# PowerBoardOld.net
KiCad netlist of a schematic drawn in Altium Designer
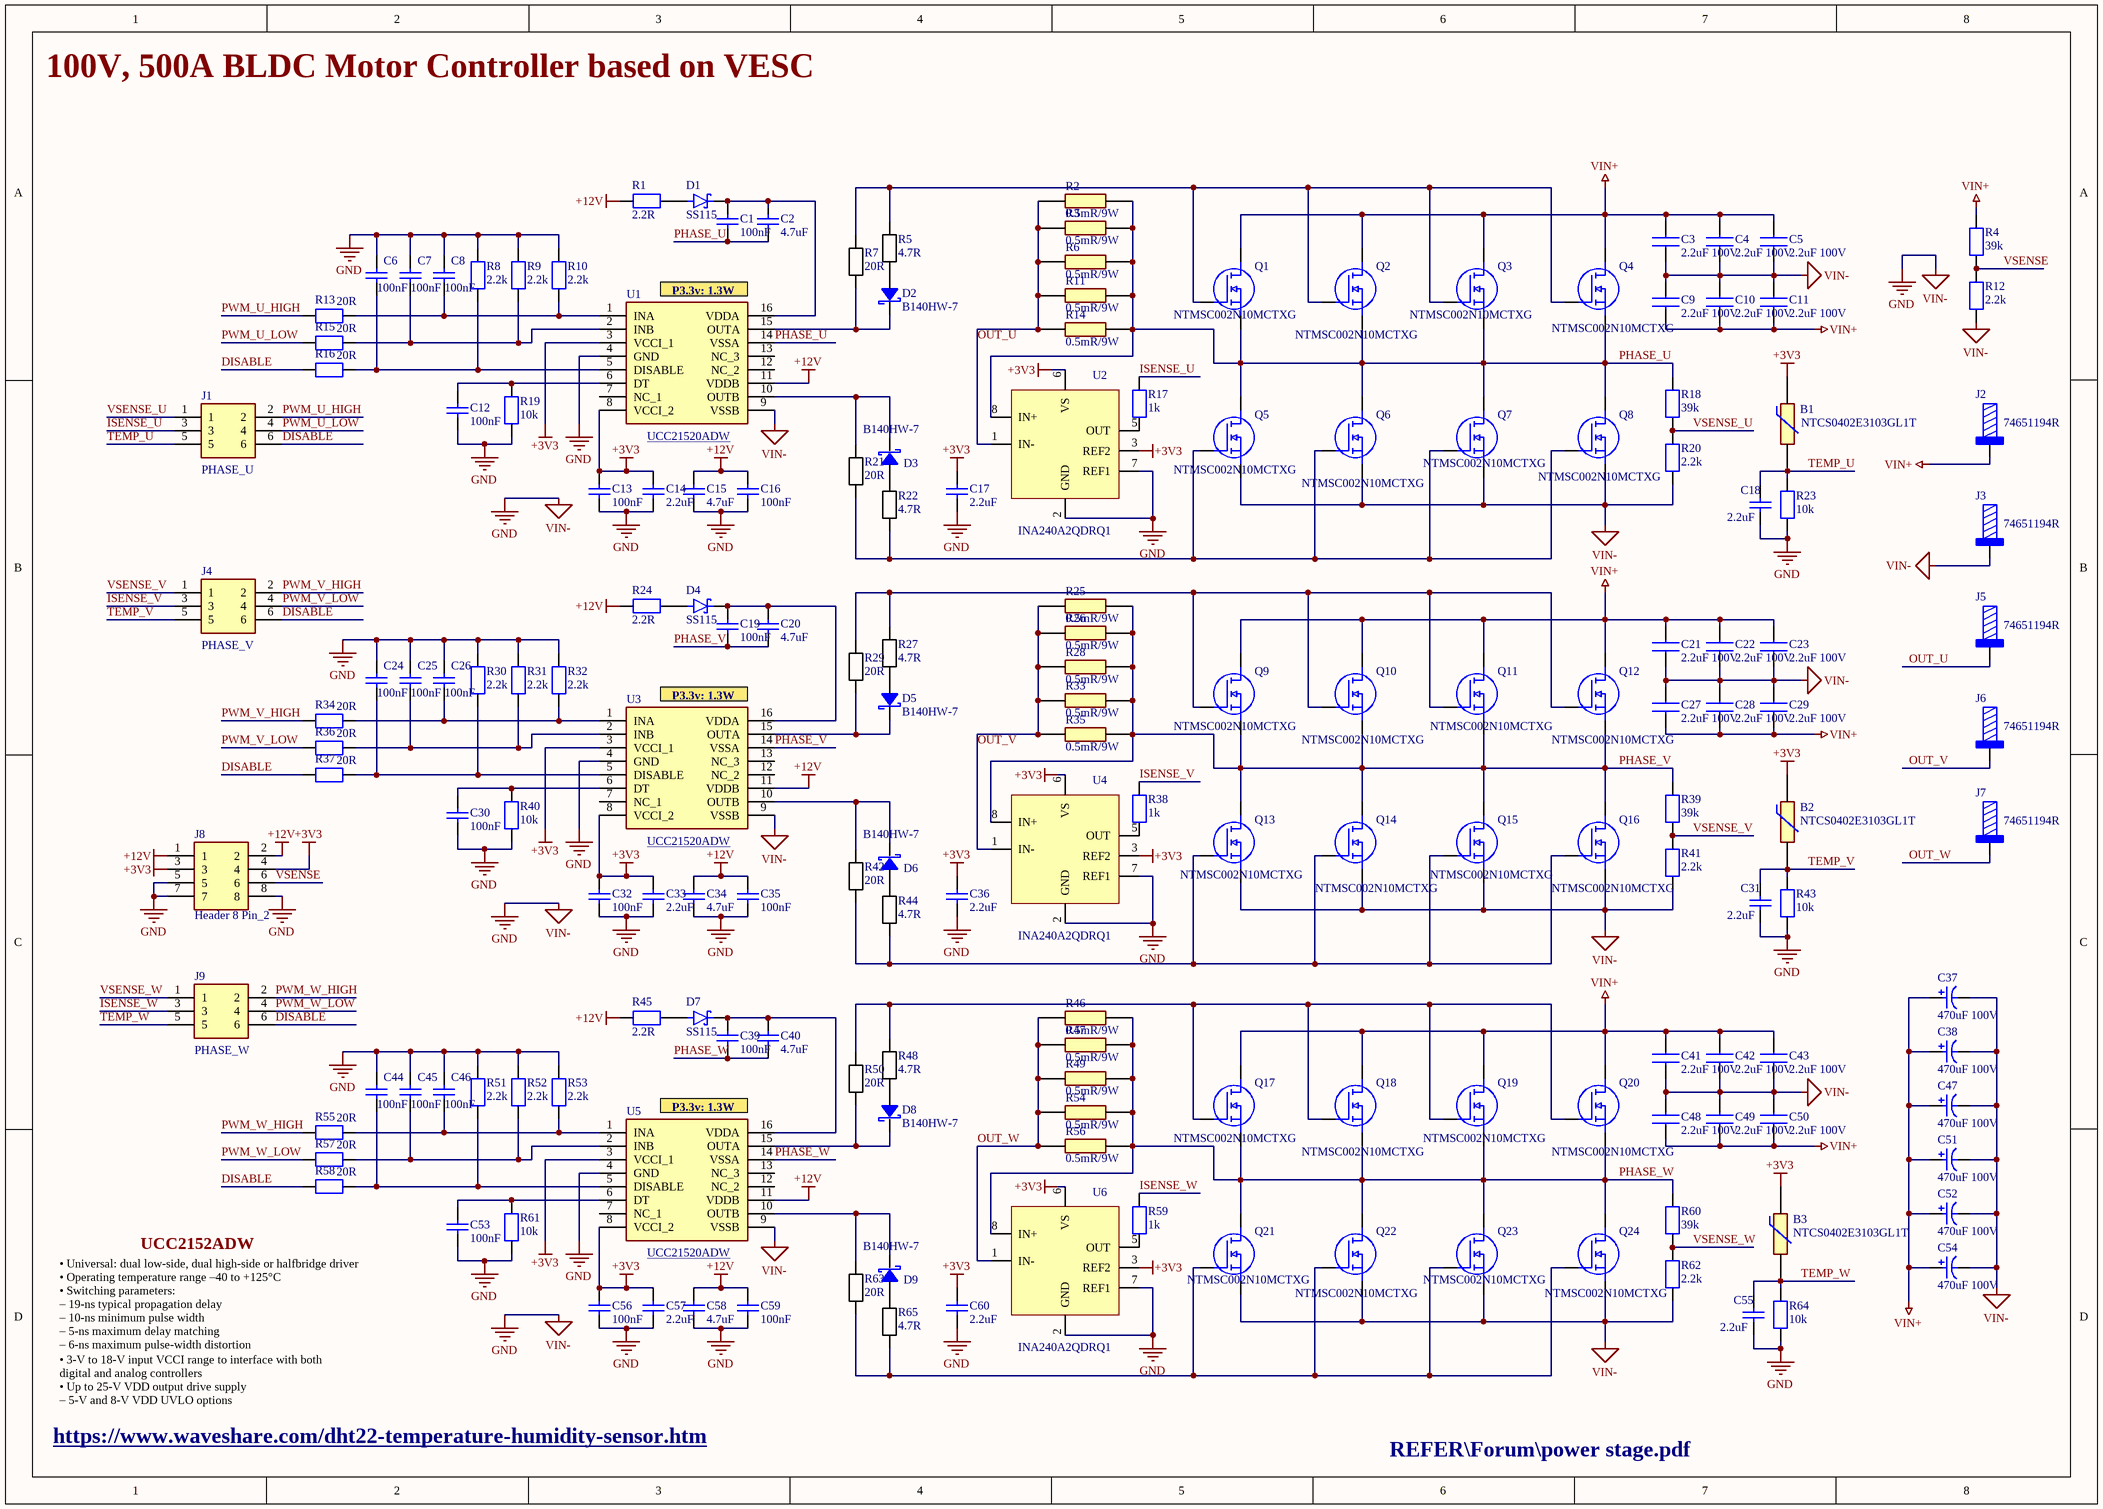
[diagram p0: PowerBoardOld.SchDoc]

(export (version "E")
  (design (tool "Eeschema 10.0.6"))
  (components
    (comp (ref "B1")
      (value "NTCS0402E3103GL1T")
      (footprint "THRMC1005X65N")
      (description "NTC Thermistors 10Kohms 2% AEC-Q200")
      (fields (field (name "MANUFACTURER") "Vishay"))
      (libsource (lib "VESC_MotorController") (part "NTCS0402E3103GL1T"))
    )
    (comp (ref "B2")
      (value "NTCS0402E3103GL1T")
      (footprint "THRMC1005X65N")
      (description "NTC Thermistors 10Kohms 2% AEC-Q200")
      (fields (field (name "MANUFACTURER") "Vishay"))
      (libsource (lib "VESC_MotorController") (part "NTCS0402E3103GL1T"))
    )
    (comp (ref "B3")
      (value "NTCS0402E3103GL1T")
      (footprint "THRMC1005X65N")
      (description "NTC Thermistors 10Kohms 2% AEC-Q200")
      (fields (field (name "MANUFACTURER") "Vishay"))
      (libsource (lib "VESC_MotorController") (part "NTCS0402E3103GL1T"))
    )
    (comp (ref "C1")
      (value "100nF")
      (footprint "C0402")
      (description "100nF ± 10% 50V")
      (fields
        (field (name "MANUFACTURER") "Yageo")
        (field (name "MANUFACTURER PART NUMBER") "CS0603KRX7R9BB104")
      )
      (libsource (lib "VESC_MotorController") (part "100nF ± 10% 50V"))
    )
    (comp (ref "C2")
      (value "4.7uF")
      (footprint "C0603")
      (description "4.7uF ± 10% 50V")
      (fields
        (field (name "MANUFACTURER") "Yageo")
        (field (name "MANUFACTURER PART NUMBER") "GRM188R61H225ME11J")
      )
      (libsource (lib "VESC_MotorController") (part "4.7uF ± 10% 50V"))
    )
    (comp (ref "C3")
      (value "2.2uF 100V")
      (footprint "CAPC3216X178N")
      (description "Multilayer Ceramic Capacitors MLCC - SMD/SMT 100V 2.2uF X7R 1206 20%TOL HIGH CV")
      (fields
        (field (name "MANUFACTURER") "KYOCERA AVX")
        (field (name "MANUFACTURER PART NUMBER") "12061C225MAT2A")
      )
      (libsource (lib "VESC_MotorController") (part "2.2uF ±10% 100V"))
    )
    (comp (ref "C4")
      (value "2.2uF 100V")
      (footprint "CAPC3216X178N")
      (description "Multilayer Ceramic Capacitors MLCC - SMD/SMT 100V 2.2uF X7R 1206 20%TOL HIGH CV")
      (fields
        (field (name "MANUFACTURER") "KYOCERA AVX")
        (field (name "MANUFACTURER PART NUMBER") "12061C225MAT2A")
      )
      (libsource (lib "VESC_MotorController") (part "2.2uF ±10% 100V"))
    )
    (comp (ref "C5")
      (value "2.2uF 100V")
      (footprint "CAPC3216X178N")
      (description "Multilayer Ceramic Capacitors MLCC - SMD/SMT 100V 2.2uF X7R 1206 20%TOL HIGH CV")
      (fields
        (field (name "MANUFACTURER") "KYOCERA AVX")
        (field (name "MANUFACTURER PART NUMBER") "12061C225MAT2A")
      )
      (libsource (lib "VESC_MotorController") (part "2.2uF ±10% 100V"))
    )
    (comp (ref "C6")
      (value "100nF")
      (footprint "C0402")
      (description "100nF ± 10% 50V")
      (fields
        (field (name "MANUFACTURER") "Yageo")
        (field (name "MANUFACTURER PART NUMBER") "CS0603KRX7R9BB104")
      )
      (libsource (lib "VESC_MotorController") (part "100nF ± 10% 50V"))
    )
    (comp (ref "C7")
      (value "100nF")
      (footprint "C0402")
      (description "100nF ± 10% 50V")
      (fields
        (field (name "MANUFACTURER") "Yageo")
        (field (name "MANUFACTURER PART NUMBER") "CS0603KRX7R9BB104")
      )
      (libsource (lib "VESC_MotorController") (part "100nF ± 10% 50V"))
    )
    (comp (ref "C8")
      (value "100nF")
      (footprint "C0402")
      (description "100nF ± 10% 50V")
      (fields
        (field (name "MANUFACTURER") "Yageo")
        (field (name "MANUFACTURER PART NUMBER") "CS0603KRX7R9BB104")
      )
      (libsource (lib "VESC_MotorController") (part "100nF ± 10% 50V"))
    )
    (comp (ref "C9")
      (value "2.2uF 100V")
      (footprint "CAPC3216X178N")
      (description "Multilayer Ceramic Capacitors MLCC - SMD/SMT 100V 2.2uF X7R 1206 20%TOL HIGH CV")
      (fields
        (field (name "MANUFACTURER") "KYOCERA AVX")
        (field (name "MANUFACTURER PART NUMBER") "12061C225MAT2A")
      )
      (libsource (lib "VESC_MotorController") (part "2.2uF ±10% 100V"))
    )
    (comp (ref "C10")
      (value "2.2uF 100V")
      (footprint "CAPC3216X178N")
      (description "Multilayer Ceramic Capacitors MLCC - SMD/SMT 100V 2.2uF X7R 1206 20%TOL HIGH CV")
      (fields
        (field (name "MANUFACTURER") "KYOCERA AVX")
        (field (name "MANUFACTURER PART NUMBER") "12061C225MAT2A")
      )
      (libsource (lib "VESC_MotorController") (part "2.2uF ±10% 100V"))
    )
    (comp (ref "C11")
      (value "2.2uF 100V")
      (footprint "CAPC3216X178N")
      (description "Multilayer Ceramic Capacitors MLCC - SMD/SMT 100V 2.2uF X7R 1206 20%TOL HIGH CV")
      (fields
        (field (name "MANUFACTURER") "KYOCERA AVX")
        (field (name "MANUFACTURER PART NUMBER") "12061C225MAT2A")
      )
      (libsource (lib "VESC_MotorController") (part "2.2uF ±10% 100V"))
    )
    (comp (ref "C12")
      (value "100nF")
      (footprint "C0402")
      (description "100nF ± 10% 50V")
      (fields
        (field (name "MANUFACTURER") "Yageo")
        (field (name "MANUFACTURER PART NUMBER") "CS0603KRX7R9BB104")
      )
      (libsource (lib "VESC_MotorController") (part "100nF ± 10% 50V"))
    )
    (comp (ref "C13")
      (value "100nF")
      (footprint "C0402")
      (description "100nF ± 10% 50V")
      (fields
        (field (name "MANUFACTURER") "Yageo")
        (field (name "MANUFACTURER PART NUMBER") "CS0603KRX7R9BB104")
      )
      (libsource (lib "VESC_MotorController") (part "100nF ± 10% 50V"))
    )
    (comp (ref "C14")
      (value "2.2uF")
      (footprint "C0603")
      (description "2.2uF ± 10% 50V")
      (fields
        (field (name "MANUFACTURER") "Yageo")
        (field (name "MANUFACTURER PART NUMBER") "GRM188R61H225ME11J")
      )
      (libsource (lib "VESC_MotorController") (part "2.2uF ± 10% 50V"))
    )
    (comp (ref "C15")
      (value "4.7uF")
      (footprint "C0603")
      (description "4.7uF ± 10% 50V")
      (fields
        (field (name "MANUFACTURER") "Yageo")
        (field (name "MANUFACTURER PART NUMBER") "GRM188R61H225ME11J")
      )
      (libsource (lib "VESC_MotorController") (part "4.7uF ± 10% 50V"))
    )
    (comp (ref "C16")
      (value "100nF")
      (footprint "C0402")
      (description "100nF ± 10% 50V")
      (fields
        (field (name "MANUFACTURER") "Yageo")
        (field (name "MANUFACTURER PART NUMBER") "CS0603KRX7R9BB104")
      )
      (libsource (lib "VESC_MotorController") (part "100nF ± 10% 50V"))
    )
    (comp (ref "C17")
      (value "2.2uF")
      (footprint "C0603")
      (description "2.2uF ± 10% 50V")
      (fields
        (field (name "MANUFACTURER") "Yageo")
        (field (name "MANUFACTURER PART NUMBER") "GRM188R61H225ME11J")
      )
      (libsource (lib "VESC_MotorController") (part "2.2uF ± 10% 50V"))
    )
    (comp (ref "C18")
      (value "2.2uF")
      (footprint "C0603")
      (description "2.2uF ± 10% 50V")
      (fields
        (field (name "MANUFACTURER") "Yageo")
        (field (name "MANUFACTURER PART NUMBER") "GRM188R61H225ME11J")
      )
      (libsource (lib "VESC_MotorController") (part "2.2uF ± 10% 50V"))
    )
    (comp (ref "C19")
      (value "100nF")
      (footprint "C0402")
      (description "100nF ± 10% 50V")
      (fields
        (field (name "MANUFACTURER") "Yageo")
        (field (name "MANUFACTURER PART NUMBER") "CS0603KRX7R9BB104")
      )
      (libsource (lib "VESC_MotorController") (part "100nF ± 10% 50V"))
    )
    (comp (ref "C20")
      (value "4.7uF")
      (footprint "C0603")
      (description "4.7uF ± 10% 50V")
      (fields
        (field (name "MANUFACTURER") "Yageo")
        (field (name "MANUFACTURER PART NUMBER") "GRM188R61H225ME11J")
      )
      (libsource (lib "VESC_MotorController") (part "4.7uF ± 10% 50V"))
    )
    (comp (ref "C21")
      (value "2.2uF 100V")
      (footprint "CAPC3216X178N")
      (description "Multilayer Ceramic Capacitors MLCC - SMD/SMT 100V 2.2uF X7R 1206 20%TOL HIGH CV")
      (fields
        (field (name "MANUFACTURER") "KYOCERA AVX")
        (field (name "MANUFACTURER PART NUMBER") "12061C225MAT2A")
      )
      (libsource (lib "VESC_MotorController") (part "2.2uF ±10% 100V"))
    )
    (comp (ref "C22")
      (value "2.2uF 100V")
      (footprint "CAPC3216X178N")
      (description "Multilayer Ceramic Capacitors MLCC - SMD/SMT 100V 2.2uF X7R 1206 20%TOL HIGH CV")
      (fields
        (field (name "MANUFACTURER") "KYOCERA AVX")
        (field (name "MANUFACTURER PART NUMBER") "12061C225MAT2A")
      )
      (libsource (lib "VESC_MotorController") (part "2.2uF ±10% 100V"))
    )
    (comp (ref "C23")
      (value "2.2uF 100V")
      (footprint "CAPC3216X178N")
      (description "Multilayer Ceramic Capacitors MLCC - SMD/SMT 100V 2.2uF X7R 1206 20%TOL HIGH CV")
      (fields
        (field (name "MANUFACTURER") "KYOCERA AVX")
        (field (name "MANUFACTURER PART NUMBER") "12061C225MAT2A")
      )
      (libsource (lib "VESC_MotorController") (part "2.2uF ±10% 100V"))
    )
    (comp (ref "C24")
      (value "100nF")
      (footprint "C0402")
      (description "100nF ± 10% 50V")
      (fields
        (field (name "MANUFACTURER") "Yageo")
        (field (name "MANUFACTURER PART NUMBER") "CS0603KRX7R9BB104")
      )
      (libsource (lib "VESC_MotorController") (part "100nF ± 10% 50V"))
    )
    (comp (ref "C25")
      (value "100nF")
      (footprint "C0402")
      (description "100nF ± 10% 50V")
      (fields
        (field (name "MANUFACTURER") "Yageo")
        (field (name "MANUFACTURER PART NUMBER") "CS0603KRX7R9BB104")
      )
      (libsource (lib "VESC_MotorController") (part "100nF ± 10% 50V"))
    )
    (comp (ref "C26")
      (value "100nF")
      (footprint "C0402")
      (description "100nF ± 10% 50V")
      (fields
        (field (name "MANUFACTURER") "Yageo")
        (field (name "MANUFACTURER PART NUMBER") "CS0603KRX7R9BB104")
      )
      (libsource (lib "VESC_MotorController") (part "100nF ± 10% 50V"))
    )
    (comp (ref "C27")
      (value "2.2uF 100V")
      (footprint "CAPC3216X178N")
      (description "Multilayer Ceramic Capacitors MLCC - SMD/SMT 100V 2.2uF X7R 1206 20%TOL HIGH CV")
      (fields
        (field (name "MANUFACTURER") "KYOCERA AVX")
        (field (name "MANUFACTURER PART NUMBER") "12061C225MAT2A")
      )
      (libsource (lib "VESC_MotorController") (part "2.2uF ±10% 100V"))
    )
    (comp (ref "C28")
      (value "2.2uF 100V")
      (footprint "CAPC3216X178N")
      (description "Multilayer Ceramic Capacitors MLCC - SMD/SMT 100V 2.2uF X7R 1206 20%TOL HIGH CV")
      (fields
        (field (name "MANUFACTURER") "KYOCERA AVX")
        (field (name "MANUFACTURER PART NUMBER") "12061C225MAT2A")
      )
      (libsource (lib "VESC_MotorController") (part "2.2uF ±10% 100V"))
    )
    (comp (ref "C29")
      (value "2.2uF 100V")
      (footprint "CAPC3216X178N")
      (description "Multilayer Ceramic Capacitors MLCC - SMD/SMT 100V 2.2uF X7R 1206 20%TOL HIGH CV")
      (fields
        (field (name "MANUFACTURER") "KYOCERA AVX")
        (field (name "MANUFACTURER PART NUMBER") "12061C225MAT2A")
      )
      (libsource (lib "VESC_MotorController") (part "2.2uF ±10% 100V"))
    )
    (comp (ref "C30")
      (value "100nF")
      (footprint "C0402")
      (description "100nF ± 10% 50V")
      (fields
        (field (name "MANUFACTURER") "Yageo")
        (field (name "MANUFACTURER PART NUMBER") "CS0603KRX7R9BB104")
      )
      (libsource (lib "VESC_MotorController") (part "100nF ± 10% 50V"))
    )
    (comp (ref "C31")
      (value "2.2uF")
      (footprint "C0603")
      (description "2.2uF ± 10% 50V")
      (fields
        (field (name "MANUFACTURER") "Yageo")
        (field (name "MANUFACTURER PART NUMBER") "GRM188R61H225ME11J")
      )
      (libsource (lib "VESC_MotorController") (part "2.2uF ± 10% 50V"))
    )
    (comp (ref "C32")
      (value "100nF")
      (footprint "C0402")
      (description "100nF ± 10% 50V")
      (fields
        (field (name "MANUFACTURER") "Yageo")
        (field (name "MANUFACTURER PART NUMBER") "CS0603KRX7R9BB104")
      )
      (libsource (lib "VESC_MotorController") (part "100nF ± 10% 50V"))
    )
    (comp (ref "C33")
      (value "2.2uF")
      (footprint "C0603")
      (description "2.2uF ± 10% 50V")
      (fields
        (field (name "MANUFACTURER") "Yageo")
        (field (name "MANUFACTURER PART NUMBER") "GRM188R61H225ME11J")
      )
      (libsource (lib "VESC_MotorController") (part "2.2uF ± 10% 50V"))
    )
    (comp (ref "C34")
      (value "4.7uF")
      (footprint "C0603")
      (description "4.7uF ± 10% 50V")
      (fields
        (field (name "MANUFACTURER") "Yageo")
        (field (name "MANUFACTURER PART NUMBER") "GRM188R61H225ME11J")
      )
      (libsource (lib "VESC_MotorController") (part "4.7uF ± 10% 50V"))
    )
    (comp (ref "C35")
      (value "100nF")
      (footprint "C0402")
      (description "100nF ± 10% 50V")
      (fields
        (field (name "MANUFACTURER") "Yageo")
        (field (name "MANUFACTURER PART NUMBER") "CS0603KRX7R9BB104")
      )
      (libsource (lib "VESC_MotorController") (part "100nF ± 10% 50V"))
    )
    (comp (ref "C36")
      (value "2.2uF")
      (footprint "C0603")
      (description "2.2uF ± 10% 50V")
      (fields
        (field (name "MANUFACTURER") "Yageo")
        (field (name "MANUFACTURER PART NUMBER") "GRM188R61H225ME11J")
      )
      (libsource (lib "VESC_MotorController") (part "2.2uF ± 10% 50V"))
    )
    (comp (ref "C37")
      (value "470uF 100V")
      (footprint "CAPPRD750W80D1625H4150")
      (description "Aluminum Electrolytic Capacitors - Radial Leaded 100volts 470uF 20% 16X35.5 7.5LS")
      (fields
        (field (name "MANUFACTURER") "Nichicon")
        (field (name "MANUFACTURER PART NUMBER") "UHE2A471MHD")
      )
      (libsource (lib "VESC_MotorController") (part "470uF 100V"))
    )
    (comp (ref "C38")
      (value "470uF 100V")
      (footprint "CAPPRD750W80D1625H4150")
      (description "Aluminum Electrolytic Capacitors - Radial Leaded 100volts 470uF 20% 16X35.5 7.5LS")
      (fields
        (field (name "MANUFACTURER") "Nichicon")
        (field (name "MANUFACTURER PART NUMBER") "UHE2A471MHD")
      )
      (libsource (lib "VESC_MotorController") (part "470uF 100V"))
    )
    (comp (ref "C39")
      (value "100nF")
      (footprint "C0402")
      (description "100nF ± 10% 50V")
      (fields
        (field (name "MANUFACTURER") "Yageo")
        (field (name "MANUFACTURER PART NUMBER") "CS0603KRX7R9BB104")
      )
      (libsource (lib "VESC_MotorController") (part "100nF ± 10% 50V"))
    )
    (comp (ref "C40")
      (value "4.7uF")
      (footprint "C0603")
      (description "4.7uF ± 10% 50V")
      (fields
        (field (name "MANUFACTURER") "Yageo")
        (field (name "MANUFACTURER PART NUMBER") "GRM188R61H225ME11J")
      )
      (libsource (lib "VESC_MotorController") (part "4.7uF ± 10% 50V"))
    )
    (comp (ref "C41")
      (value "2.2uF 100V")
      (footprint "CAPC3216X178N")
      (description "Multilayer Ceramic Capacitors MLCC - SMD/SMT 100V 2.2uF X7R 1206 20%TOL HIGH CV")
      (fields
        (field (name "MANUFACTURER") "KYOCERA AVX")
        (field (name "MANUFACTURER PART NUMBER") "12061C225MAT2A")
      )
      (libsource (lib "VESC_MotorController") (part "2.2uF ±10% 100V"))
    )
    (comp (ref "C42")
      (value "2.2uF 100V")
      (footprint "CAPC3216X178N")
      (description "Multilayer Ceramic Capacitors MLCC - SMD/SMT 100V 2.2uF X7R 1206 20%TOL HIGH CV")
      (fields
        (field (name "MANUFACTURER") "KYOCERA AVX")
        (field (name "MANUFACTURER PART NUMBER") "12061C225MAT2A")
      )
      (libsource (lib "VESC_MotorController") (part "2.2uF ±10% 100V"))
    )
    (comp (ref "C43")
      (value "2.2uF 100V")
      (footprint "CAPC3216X178N")
      (description "Multilayer Ceramic Capacitors MLCC - SMD/SMT 100V 2.2uF X7R 1206 20%TOL HIGH CV")
      (fields
        (field (name "MANUFACTURER") "KYOCERA AVX")
        (field (name "MANUFACTURER PART NUMBER") "12061C225MAT2A")
      )
      (libsource (lib "VESC_MotorController") (part "2.2uF ±10% 100V"))
    )
    (comp (ref "C44")
      (value "100nF")
      (footprint "C0402")
      (description "100nF ± 10% 50V")
      (fields
        (field (name "MANUFACTURER") "Yageo")
        (field (name "MANUFACTURER PART NUMBER") "CS0603KRX7R9BB104")
      )
      (libsource (lib "VESC_MotorController") (part "100nF ± 10% 50V"))
    )
    (comp (ref "C45")
      (value "100nF")
      (footprint "C0402")
      (description "100nF ± 10% 50V")
      (fields
        (field (name "MANUFACTURER") "Yageo")
        (field (name "MANUFACTURER PART NUMBER") "CS0603KRX7R9BB104")
      )
      (libsource (lib "VESC_MotorController") (part "100nF ± 10% 50V"))
    )
    (comp (ref "C46")
      (value "100nF")
      (footprint "C0402")
      (description "100nF ± 10% 50V")
      (fields
        (field (name "MANUFACTURER") "Yageo")
        (field (name "MANUFACTURER PART NUMBER") "CS0603KRX7R9BB104")
      )
      (libsource (lib "VESC_MotorController") (part "100nF ± 10% 50V"))
    )
    (comp (ref "C47")
      (value "470uF 100V")
      (footprint "CAPPRD750W80D1625H4150")
      (description "Aluminum Electrolytic Capacitors - Radial Leaded 100volts 470uF 20% 16X35.5 7.5LS")
      (fields
        (field (name "MANUFACTURER") "Nichicon")
        (field (name "MANUFACTURER PART NUMBER") "UHE2A471MHD")
      )
      (libsource (lib "VESC_MotorController") (part "470uF 100V"))
    )
    (comp (ref "C48")
      (value "2.2uF 100V")
      (footprint "CAPC3216X178N")
      (description "Multilayer Ceramic Capacitors MLCC - SMD/SMT 100V 2.2uF X7R 1206 20%TOL HIGH CV")
      (fields
        (field (name "MANUFACTURER") "KYOCERA AVX")
        (field (name "MANUFACTURER PART NUMBER") "12061C225MAT2A")
      )
      (libsource (lib "VESC_MotorController") (part "2.2uF ±10% 100V"))
    )
    (comp (ref "C49")
      (value "2.2uF 100V")
      (footprint "CAPC3216X178N")
      (description "Multilayer Ceramic Capacitors MLCC - SMD/SMT 100V 2.2uF X7R 1206 20%TOL HIGH CV")
      (fields
        (field (name "MANUFACTURER") "KYOCERA AVX")
        (field (name "MANUFACTURER PART NUMBER") "12061C225MAT2A")
      )
      (libsource (lib "VESC_MotorController") (part "2.2uF ±10% 100V"))
    )
    (comp (ref "C50")
      (value "2.2uF 100V")
      (footprint "CAPC3216X178N")
      (description "Multilayer Ceramic Capacitors MLCC - SMD/SMT 100V 2.2uF X7R 1206 20%TOL HIGH CV")
      (fields
        (field (name "MANUFACTURER") "KYOCERA AVX")
        (field (name "MANUFACTURER PART NUMBER") "12061C225MAT2A")
      )
      (libsource (lib "VESC_MotorController") (part "2.2uF ±10% 100V"))
    )
    (comp (ref "C51")
      (value "470uF 100V")
      (footprint "CAPPRD750W80D1625H4150")
      (description "Aluminum Electrolytic Capacitors - Radial Leaded 100volts 470uF 20% 16X35.5 7.5LS")
      (fields
        (field (name "MANUFACTURER") "Nichicon")
        (field (name "MANUFACTURER PART NUMBER") "UHE2A471MHD")
      )
      (libsource (lib "VESC_MotorController") (part "470uF 100V"))
    )
    (comp (ref "C52")
      (value "470uF 100V")
      (footprint "CAPPRD750W80D1625H4150")
      (description "Aluminum Electrolytic Capacitors - Radial Leaded 100volts 470uF 20% 16X35.5 7.5LS")
      (fields
        (field (name "MANUFACTURER") "Nichicon")
        (field (name "MANUFACTURER PART NUMBER") "UHE2A471MHD")
      )
      (libsource (lib "VESC_MotorController") (part "470uF 100V"))
    )
    (comp (ref "C53")
      (value "100nF")
      (footprint "C0402")
      (description "100nF ± 10% 50V")
      (fields
        (field (name "MANUFACTURER") "Yageo")
        (field (name "MANUFACTURER PART NUMBER") "CS0603KRX7R9BB104")
      )
      (libsource (lib "VESC_MotorController") (part "100nF ± 10% 50V"))
    )
    (comp (ref "C54")
      (value "470uF 100V")
      (footprint "CAPPRD750W80D1625H4150")
      (description "Aluminum Electrolytic Capacitors - Radial Leaded 100volts 470uF 20% 16X35.5 7.5LS")
      (fields
        (field (name "MANUFACTURER") "Nichicon")
        (field (name "MANUFACTURER PART NUMBER") "UHE2A471MHD")
      )
      (libsource (lib "VESC_MotorController") (part "470uF 100V"))
    )
    (comp (ref "C55")
      (value "2.2uF")
      (footprint "C0603")
      (description "2.2uF ± 10% 50V")
      (fields
        (field (name "MANUFACTURER") "Yageo")
        (field (name "MANUFACTURER PART NUMBER") "GRM188R61H225ME11J")
      )
      (libsource (lib "VESC_MotorController") (part "2.2uF ± 10% 50V"))
    )
    (comp (ref "C56")
      (value "100nF")
      (footprint "C0402")
      (description "100nF ± 10% 50V")
      (fields
        (field (name "MANUFACTURER") "Yageo")
        (field (name "MANUFACTURER PART NUMBER") "CS0603KRX7R9BB104")
      )
      (libsource (lib "VESC_MotorController") (part "100nF ± 10% 50V"))
    )
    (comp (ref "C57")
      (value "2.2uF")
      (footprint "C0603")
      (description "2.2uF ± 10% 50V")
      (fields
        (field (name "MANUFACTURER") "Yageo")
        (field (name "MANUFACTURER PART NUMBER") "GRM188R61H225ME11J")
      )
      (libsource (lib "VESC_MotorController") (part "2.2uF ± 10% 50V"))
    )
    (comp (ref "C58")
      (value "4.7uF")
      (footprint "C0603")
      (description "4.7uF ± 10% 50V")
      (fields
        (field (name "MANUFACTURER") "Yageo")
        (field (name "MANUFACTURER PART NUMBER") "GRM188R61H225ME11J")
      )
      (libsource (lib "VESC_MotorController") (part "4.7uF ± 10% 50V"))
    )
    (comp (ref "C59")
      (value "100nF")
      (footprint "C0402")
      (description "100nF ± 10% 50V")
      (fields
        (field (name "MANUFACTURER") "Yageo")
        (field (name "MANUFACTURER PART NUMBER") "CS0603KRX7R9BB104")
      )
      (libsource (lib "VESC_MotorController") (part "100nF ± 10% 50V"))
    )
    (comp (ref "C60")
      (value "2.2uF")
      (footprint "C0603")
      (description "2.2uF ± 10% 50V")
      (fields
        (field (name "MANUFACTURER") "Yageo")
        (field (name "MANUFACTURER PART NUMBER") "GRM188R61H225ME11J")
      )
      (libsource (lib "VESC_MotorController") (part "2.2uF ± 10% 50V"))
    )
    (comp (ref "D1")
      (value "SS115")
      (footprint "DIOM4325X250N")
      (description "Schottky Diodes & Rectifiers 1A, 150V, Schottky Rectifier")
      (fields (field (name "MANUFACTURER") "Taiwan Semiconductor"))
      (libsource (lib "VESC_MotorController") (part "SS115"))
    )
    (comp (ref "D2")
      (value "B140HW-7")
      (footprint "SOD123")
      (description "Schottky Diodes & Rectifiers 1A, 40V")
      (fields (field (name "MANUFACTURER") "Diodes"))
      (libsource (lib "VESC_MotorController") (part "B140HW-7"))
    )
    (comp (ref "D3")
      (value "B140HW-7")
      (footprint "SOD123")
      (description "Schottky Diodes & Rectifiers 1A, 40V")
      (fields (field (name "MANUFACTURER") "Diodes"))
      (libsource (lib "VESC_MotorController") (part "B140HW-7"))
    )
    (comp (ref "D4")
      (value "SS115")
      (footprint "DIOM4325X250N")
      (description "Schottky Diodes & Rectifiers 1A, 150V, Schottky Rectifier")
      (fields (field (name "MANUFACTURER") "Taiwan Semiconductor"))
      (libsource (lib "VESC_MotorController") (part "SS115"))
    )
    (comp (ref "D5")
      (value "B140HW-7")
      (footprint "SOD123")
      (description "Schottky Diodes & Rectifiers 1A, 40V")
      (fields (field (name "MANUFACTURER") "Diodes"))
      (libsource (lib "VESC_MotorController") (part "B140HW-7"))
    )
    (comp (ref "D6")
      (value "B140HW-7")
      (footprint "SOD123")
      (description "Schottky Diodes & Rectifiers 1A, 40V")
      (fields (field (name "MANUFACTURER") "Diodes"))
      (libsource (lib "VESC_MotorController") (part "B140HW-7"))
    )
    (comp (ref "D7")
      (value "SS115")
      (footprint "DIOM4325X250N")
      (description "Schottky Diodes & Rectifiers 1A, 150V, Schottky Rectifier")
      (fields (field (name "MANUFACTURER") "Taiwan Semiconductor"))
      (libsource (lib "VESC_MotorController") (part "SS115"))
    )
    (comp (ref "D8")
      (value "B140HW-7")
      (footprint "SOD123")
      (description "Schottky Diodes & Rectifiers 1A, 40V")
      (fields (field (name "MANUFACTURER") "Diodes"))
      (libsource (lib "VESC_MotorController") (part "B140HW-7"))
    )
    (comp (ref "D9")
      (value "B140HW-7")
      (footprint "SOD123")
      (description "Schottky Diodes & Rectifiers 1A, 40V")
      (fields (field (name "MANUFACTURER") "Diodes"))
      (libsource (lib "VESC_MotorController") (part "B140HW-7"))
    )
    (comp (ref "J1")
      (value "PHASE_U")
      (footprint "61300621121")
      (fields
        (field (name "MANUFACTURER") "Wurth Elektronik")
        (field (name "MANUFACTURER PART NUMBER") "61300621121")
      )
      (libsource (lib "VESC_MotorController") (part "Header 6 Pin_2"))
    )
    (comp (ref "J2")
      (value "74651194R")
      (footprint "74651194")
      (description "WP-THRSH REDCUBE THR with external thread, M4 x 5mm, 85A")
      (fields (field (name "MANUFACTURER") "Wurth Elektronik"))
      (libsource (lib "WP-THRSH") (part "74651194R"))
    )
    (comp (ref "J3")
      (value "74651194R")
      (footprint "74651194")
      (description "WP-THRSH REDCUBE THR with external thread, M4 x 5mm, 85A")
      (fields (field (name "MANUFACTURER") "Wurth Elektronik"))
      (libsource (lib "WP-THRSH") (part "74651194R"))
    )
    (comp (ref "J4")
      (value "PHASE_V")
      (footprint "61300621121")
      (fields
        (field (name "MANUFACTURER") "Wurth Elektronik")
        (field (name "MANUFACTURER PART NUMBER") "61300621121")
      )
      (libsource (lib "VESC_MotorController") (part "Header 6 Pin_2"))
    )
    (comp (ref "J5")
      (value "74651194R")
      (footprint "74651194")
      (description "WP-THRSH REDCUBE THR with external thread, M4 x 5mm, 85A")
      (fields (field (name "MANUFACTURER") "Wurth Elektronik"))
      (libsource (lib "WP-THRSH") (part "74651194R"))
    )
    (comp (ref "J6")
      (value "74651194R")
      (footprint "74651194")
      (description "WP-THRSH REDCUBE THR with external thread, M4 x 5mm, 85A")
      (fields (field (name "MANUFACTURER") "Wurth Elektronik"))
      (libsource (lib "WP-THRSH") (part "74651194R"))
    )
    (comp (ref "J7")
      (value "74651194R")
      (footprint "74651194")
      (description "WP-THRSH REDCUBE THR with external thread, M4 x 5mm, 85A")
      (fields (field (name "MANUFACTURER") "Wurth Elektronik"))
      (libsource (lib "WP-THRSH") (part "74651194R"))
    )
    (comp (ref "J8")
      (value "Header 8 Pin_2")
      (footprint "61300821121")
      (description "Headers & Wire Housings WR-PHD 2.54mm Hdr 8P Dual Str Gold")
      (fields
        (field (name "MANUFACTURER") "Wurth Elektronik")
        (field (name "MANUFACTURER PART NUMBER") "61300821121")
      )
      (libsource (lib "VESC_MotorController") (part "Header 8 Pin_2"))
    )
    (comp (ref "J9")
      (value "PHASE_W")
      (footprint "61300621121")
      (fields
        (field (name "MANUFACTURER") "Wurth Elektronik")
        (field (name "MANUFACTURER PART NUMBER") "61300621121")
      )
      (libsource (lib "VESC_MotorController") (part "Header 6 Pin_2"))
    )
    (comp (ref "Q1")
      (value "NTMSC002N10MCTXG")
      (footprint "NTMSC002N10MCTXG")
      (description "MOSFET Single N-Channel Power MOSFET 100V, 236A, 2.0mohm")
      (fields
        (field (name "MANUFACTURER") "Onsemi")
        (field (name "MANUFACTURER PART NUMBER") "NTMTSC002N10MCTXG")
      )
      (libsource (lib "VESC_MotorController") (part "NTMSC002N10MCTXG"))
    )
    (comp (ref "Q2")
      (value "NTMSC002N10MCTXG")
      (footprint "NTMSC002N10MCTXG")
      (description "MOSFET Single N-Channel Power MOSFET 100V, 236A, 2.0mohm")
      (fields
        (field (name "MANUFACTURER") "Onsemi")
        (field (name "MANUFACTURER PART NUMBER") "NTMTSC002N10MCTXG")
      )
      (libsource (lib "VESC_MotorController") (part "NTMSC002N10MCTXG"))
    )
    (comp (ref "Q3")
      (value "NTMSC002N10MCTXG")
      (footprint "NTMSC002N10MCTXG")
      (description "MOSFET Single N-Channel Power MOSFET 100V, 236A, 2.0mohm")
      (fields
        (field (name "MANUFACTURER") "Onsemi")
        (field (name "MANUFACTURER PART NUMBER") "NTMTSC002N10MCTXG")
      )
      (libsource (lib "VESC_MotorController") (part "NTMSC002N10MCTXG"))
    )
    (comp (ref "Q4")
      (value "NTMSC002N10MCTXG")
      (footprint "NTMSC002N10MCTXG")
      (description "MOSFET Single N-Channel Power MOSFET 100V, 236A, 2.0mohm")
      (fields
        (field (name "MANUFACTURER") "Onsemi")
        (field (name "MANUFACTURER PART NUMBER") "NTMTSC002N10MCTXG")
      )
      (libsource (lib "VESC_MotorController") (part "NTMSC002N10MCTXG"))
    )
    (comp (ref "Q5")
      (value "NTMSC002N10MCTXG")
      (footprint "NTMSC002N10MCTXG")
      (description "MOSFET Single N-Channel Power MOSFET 100V, 236A, 2.0mohm")
      (fields
        (field (name "MANUFACTURER") "Onsemi")
        (field (name "MANUFACTURER PART NUMBER") "NTMTSC002N10MCTXG")
      )
      (libsource (lib "VESC_MotorController") (part "NTMSC002N10MCTXG"))
    )
    (comp (ref "Q6")
      (value "NTMSC002N10MCTXG")
      (footprint "NTMSC002N10MCTXG")
      (description "MOSFET Single N-Channel Power MOSFET 100V, 236A, 2.0mohm")
      (fields
        (field (name "MANUFACTURER") "Onsemi")
        (field (name "MANUFACTURER PART NUMBER") "NTMTSC002N10MCTXG")
      )
      (libsource (lib "VESC_MotorController") (part "NTMSC002N10MCTXG"))
    )
    (comp (ref "Q7")
      (value "NTMSC002N10MCTXG")
      (footprint "NTMSC002N10MCTXG")
      (description "MOSFET Single N-Channel Power MOSFET 100V, 236A, 2.0mohm")
      (fields
        (field (name "MANUFACTURER") "Onsemi")
        (field (name "MANUFACTURER PART NUMBER") "NTMTSC002N10MCTXG")
      )
      (libsource (lib "VESC_MotorController") (part "NTMSC002N10MCTXG"))
    )
    (comp (ref "Q8")
      (value "NTMSC002N10MCTXG")
      (footprint "NTMSC002N10MCTXG")
      (description "MOSFET Single N-Channel Power MOSFET 100V, 236A, 2.0mohm")
      (fields
        (field (name "MANUFACTURER") "Onsemi")
        (field (name "MANUFACTURER PART NUMBER") "NTMTSC002N10MCTXG")
      )
      (libsource (lib "VESC_MotorController") (part "NTMSC002N10MCTXG"))
    )
    (comp (ref "Q9")
      (value "NTMSC002N10MCTXG")
      (footprint "NTMSC002N10MCTXG")
      (description "MOSFET Single N-Channel Power MOSFET 100V, 236A, 2.0mohm")
      (fields
        (field (name "MANUFACTURER") "Onsemi")
        (field (name "MANUFACTURER PART NUMBER") "NTMTSC002N10MCTXG")
      )
      (libsource (lib "VESC_MotorController") (part "NTMSC002N10MCTXG"))
    )
    (comp (ref "Q10")
      (value "NTMSC002N10MCTXG")
      (footprint "NTMSC002N10MCTXG")
      (description "MOSFET Single N-Channel Power MOSFET 100V, 236A, 2.0mohm")
      (fields
        (field (name "MANUFACTURER") "Onsemi")
        (field (name "MANUFACTURER PART NUMBER") "NTMTSC002N10MCTXG")
      )
      (libsource (lib "VESC_MotorController") (part "NTMSC002N10MCTXG"))
    )
    (comp (ref "Q11")
      (value "NTMSC002N10MCTXG")
      (footprint "NTMSC002N10MCTXG")
      (description "MOSFET Single N-Channel Power MOSFET 100V, 236A, 2.0mohm")
      (fields
        (field (name "MANUFACTURER") "Onsemi")
        (field (name "MANUFACTURER PART NUMBER") "NTMTSC002N10MCTXG")
      )
      (libsource (lib "VESC_MotorController") (part "NTMSC002N10MCTXG"))
    )
    (comp (ref "Q12")
      (value "NTMSC002N10MCTXG")
      (footprint "NTMSC002N10MCTXG")
      (description "MOSFET Single N-Channel Power MOSFET 100V, 236A, 2.0mohm")
      (fields
        (field (name "MANUFACTURER") "Onsemi")
        (field (name "MANUFACTURER PART NUMBER") "NTMTSC002N10MCTXG")
      )
      (libsource (lib "VESC_MotorController") (part "NTMSC002N10MCTXG"))
    )
    (comp (ref "Q13")
      (value "NTMSC002N10MCTXG")
      (footprint "NTMSC002N10MCTXG")
      (description "MOSFET Single N-Channel Power MOSFET 100V, 236A, 2.0mohm")
      (fields
        (field (name "MANUFACTURER") "Onsemi")
        (field (name "MANUFACTURER PART NUMBER") "NTMTSC002N10MCTXG")
      )
      (libsource (lib "VESC_MotorController") (part "NTMSC002N10MCTXG"))
    )
    (comp (ref "Q14")
      (value "NTMSC002N10MCTXG")
      (footprint "NTMSC002N10MCTXG")
      (description "MOSFET Single N-Channel Power MOSFET 100V, 236A, 2.0mohm")
      (fields
        (field (name "MANUFACTURER") "Onsemi")
        (field (name "MANUFACTURER PART NUMBER") "NTMTSC002N10MCTXG")
      )
      (libsource (lib "VESC_MotorController") (part "NTMSC002N10MCTXG"))
    )
    (comp (ref "Q15")
      (value "NTMSC002N10MCTXG")
      (footprint "NTMSC002N10MCTXG")
      (description "MOSFET Single N-Channel Power MOSFET 100V, 236A, 2.0mohm")
      (fields
        (field (name "MANUFACTURER") "Onsemi")
        (field (name "MANUFACTURER PART NUMBER") "NTMTSC002N10MCTXG")
      )
      (libsource (lib "VESC_MotorController") (part "NTMSC002N10MCTXG"))
    )
    (comp (ref "Q16")
      (value "NTMSC002N10MCTXG")
      (footprint "NTMSC002N10MCTXG")
      (description "MOSFET Single N-Channel Power MOSFET 100V, 236A, 2.0mohm")
      (fields
        (field (name "MANUFACTURER") "Onsemi")
        (field (name "MANUFACTURER PART NUMBER") "NTMTSC002N10MCTXG")
      )
      (libsource (lib "VESC_MotorController") (part "NTMSC002N10MCTXG"))
    )
    (comp (ref "Q17")
      (value "NTMSC002N10MCTXG")
      (footprint "NTMSC002N10MCTXG")
      (description "MOSFET Single N-Channel Power MOSFET 100V, 236A, 2.0mohm")
      (fields
        (field (name "MANUFACTURER") "Onsemi")
        (field (name "MANUFACTURER PART NUMBER") "NTMTSC002N10MCTXG")
      )
      (libsource (lib "VESC_MotorController") (part "NTMSC002N10MCTXG"))
    )
    (comp (ref "Q18")
      (value "NTMSC002N10MCTXG")
      (footprint "NTMSC002N10MCTXG")
      (description "MOSFET Single N-Channel Power MOSFET 100V, 236A, 2.0mohm")
      (fields
        (field (name "MANUFACTURER") "Onsemi")
        (field (name "MANUFACTURER PART NUMBER") "NTMTSC002N10MCTXG")
      )
      (libsource (lib "VESC_MotorController") (part "NTMSC002N10MCTXG"))
    )
    (comp (ref "Q19")
      (value "NTMSC002N10MCTXG")
      (footprint "NTMSC002N10MCTXG")
      (description "MOSFET Single N-Channel Power MOSFET 100V, 236A, 2.0mohm")
      (fields
        (field (name "MANUFACTURER") "Onsemi")
        (field (name "MANUFACTURER PART NUMBER") "NTMTSC002N10MCTXG")
      )
      (libsource (lib "VESC_MotorController") (part "NTMSC002N10MCTXG"))
    )
    (comp (ref "Q20")
      (value "NTMSC002N10MCTXG")
      (footprint "NTMSC002N10MCTXG")
      (description "MOSFET Single N-Channel Power MOSFET 100V, 236A, 2.0mohm")
      (fields
        (field (name "MANUFACTURER") "Onsemi")
        (field (name "MANUFACTURER PART NUMBER") "NTMTSC002N10MCTXG")
      )
      (libsource (lib "VESC_MotorController") (part "NTMSC002N10MCTXG"))
    )
    (comp (ref "Q21")
      (value "NTMSC002N10MCTXG")
      (footprint "NTMSC002N10MCTXG")
      (description "MOSFET Single N-Channel Power MOSFET 100V, 236A, 2.0mohm")
      (fields
        (field (name "MANUFACTURER") "Onsemi")
        (field (name "MANUFACTURER PART NUMBER") "NTMTSC002N10MCTXG")
      )
      (libsource (lib "VESC_MotorController") (part "NTMSC002N10MCTXG"))
    )
    (comp (ref "Q22")
      (value "NTMSC002N10MCTXG")
      (footprint "NTMSC002N10MCTXG")
      (description "MOSFET Single N-Channel Power MOSFET 100V, 236A, 2.0mohm")
      (fields
        (field (name "MANUFACTURER") "Onsemi")
        (field (name "MANUFACTURER PART NUMBER") "NTMTSC002N10MCTXG")
      )
      (libsource (lib "VESC_MotorController") (part "NTMSC002N10MCTXG"))
    )
    (comp (ref "Q23")
      (value "NTMSC002N10MCTXG")
      (footprint "NTMSC002N10MCTXG")
      (description "MOSFET Single N-Channel Power MOSFET 100V, 236A, 2.0mohm")
      (fields
        (field (name "MANUFACTURER") "Onsemi")
        (field (name "MANUFACTURER PART NUMBER") "NTMTSC002N10MCTXG")
      )
      (libsource (lib "VESC_MotorController") (part "NTMSC002N10MCTXG"))
    )
    (comp (ref "Q24")
      (value "NTMSC002N10MCTXG")
      (footprint "NTMSC002N10MCTXG")
      (description "MOSFET Single N-Channel Power MOSFET 100V, 236A, 2.0mohm")
      (fields
        (field (name "MANUFACTURER") "Onsemi")
        (field (name "MANUFACTURER PART NUMBER") "NTMTSC002N10MCTXG")
      )
      (libsource (lib "VESC_MotorController") (part "NTMSC002N10MCTXG"))
    )
    (comp (ref "R1")
      (value "2.2R")
      (footprint "R1206")
      (description "2.2 ohm 0.25W ±1%")
      (fields
        (field (name "MANUFACTURER PART NUMBER") "RC1206FR-072R2L")
        (field (name "MANUFACTURER") "Yageo")
      )
      (libsource (lib "VESC_MotorController") (part "2.2ohm 0.25W ±1%"))
    )
    (comp (ref "R2")
      (value "0.5mR/9W")
      (footprint "RESC10052X137N")
      (description "Current Sense Resistors - SMD 0.5mOHMS 9W 1% AEC-Q200")
      (fields
        (field (name "MANUFACTURER") "Bourns")
        (field (name "MANUFACTURER PART NUMBER") "CSS2H-3920R-L500FE")
      )
      (libsource (lib "VESC_MotorController") (part "CSS2H-3920R-L500FE"))
    )
    (comp (ref "R3")
      (value "0.5mR/9W")
      (footprint "RESC10052X137N")
      (description "Current Sense Resistors - SMD 0.5mOHMS 9W 1% AEC-Q200")
      (fields
        (field (name "MANUFACTURER") "Bourns")
        (field (name "MANUFACTURER PART NUMBER") "CSS2H-3920R-L500FE")
      )
      (libsource (lib "VESC_MotorController") (part "CSS2H-3920R-L500FE"))
    )
    (comp (ref "R4")
      (value "39k")
      (footprint "R0805")
      (description "39 kOhms ±1% 0.8W")
      (fields
        (field (name "MANUFACTURER") "Yageo")
        (field (name "MANUFACTURER PART NUMBER") "RT0805FRE0739KL")
      )
      (libsource (lib "VESC_MotorController") (part "39 kOhms ±1% 0.8W"))
    )
    (comp (ref "R5")
      (value "4.7R")
      (footprint "R1206")
      (description "4.7 ohm 0.25W ±1%")
      (fields
        (field (name "MANUFACTURER PART NUMBER") "RC1206FR-074R7L")
        (field (name "MANUFACTURER") "Yageo")
      )
      (libsource (lib "VESC_MotorController") (part "4.7 ohm 0.25W ±1%"))
    )
    (comp (ref "R6")
      (value "0.5mR/9W")
      (footprint "RESC10052X137N")
      (description "Current Sense Resistors - SMD 0.5mOHMS 9W 1% AEC-Q200")
      (fields
        (field (name "MANUFACTURER") "Bourns")
        (field (name "MANUFACTURER PART NUMBER") "CSS2H-3920R-L500FE")
      )
      (libsource (lib "VESC_MotorController") (part "CSS2H-3920R-L500FE"))
    )
    (comp (ref "R7")
      (value "20R")
      (footprint "R1206")
      (description "20 ohm 0.25W ±1%")
      (fields
        (field (name "MANUFACTURER PART NUMBER") "RC1206FR-0720RL")
        (field (name "MANUFACTURER") "Yageo")
      )
      (libsource (lib "VESC_MotorController") (part "20 ohm 0.25W ±1%"))
    )
    (comp (ref "R8")
      (value "2.2k")
      (footprint "R0603")
      (description "2.2 kOhms ±1% 0.1W")
      (fields
        (field (name "MANUFACTURER") "Yageo")
        (field (name "MANUFACTURER PART NUMBER") "RC0603FR-072K2L")
      )
      (libsource (lib "VESC_MotorController") (part "2.2 kOhms ±1% 0.1W"))
    )
    (comp (ref "R9")
      (value "2.2k")
      (footprint "R0603")
      (description "2.2 kOhms ±1% 0.1W")
      (fields
        (field (name "MANUFACTURER") "Yageo")
        (field (name "MANUFACTURER PART NUMBER") "RC0603FR-072K2L")
      )
      (libsource (lib "VESC_MotorController") (part "2.2 kOhms ±1% 0.1W"))
    )
    (comp (ref "R10")
      (value "2.2k")
      (footprint "R0603")
      (description "2.2 kOhms ±1% 0.1W")
      (fields
        (field (name "MANUFACTURER") "Yageo")
        (field (name "MANUFACTURER PART NUMBER") "RC0603FR-072K2L")
      )
      (libsource (lib "VESC_MotorController") (part "2.2 kOhms ±1% 0.1W"))
    )
    (comp (ref "R11")
      (value "0.5mR/9W")
      (footprint "RESC10052X137N")
      (description "Current Sense Resistors - SMD 0.5mOHMS 9W 1% AEC-Q200")
      (fields
        (field (name "MANUFACTURER") "Bourns")
        (field (name "MANUFACTURER PART NUMBER") "CSS2H-3920R-L500FE")
      )
      (libsource (lib "VESC_MotorController") (part "CSS2H-3920R-L500FE"))
    )
    (comp (ref "R12")
      (value "2.2k")
      (footprint "R0805")
      (description "2.2 kOhms ±1% 0.8W")
      (fields
        (field (name "MANUFACTURER") "Yageo")
        (field (name "MANUFACTURER PART NUMBER") "RT0805FRE072K2L")
      )
      (libsource (lib "VESC_MotorController") (part "2.2 kOhms ±1% 0.8W"))
    )
    (comp (ref "R13")
      (value "20R")
      (footprint "R1206")
      (description "20 ohm 0.25W ±1%")
      (fields
        (field (name "MANUFACTURER PART NUMBER") "RC1206FR-0720RL")
        (field (name "MANUFACTURER") "Yageo")
      )
      (libsource (lib "VESC_MotorController") (part "20ohm 0.25W ±1%"))
    )
    (comp (ref "R14")
      (value "0.5mR/9W")
      (footprint "RESC10052X137N")
      (description "Current Sense Resistors - SMD 0.5mOHMS 9W 1% AEC-Q200")
      (fields
        (field (name "MANUFACTURER") "Bourns")
        (field (name "MANUFACTURER PART NUMBER") "CSS2H-3920R-L500FE")
      )
      (libsource (lib "VESC_MotorController") (part "CSS2H-3920R-L500FE"))
    )
    (comp (ref "R15")
      (value "20R")
      (footprint "R1206")
      (description "20 ohm 0.25W ±1%")
      (fields
        (field (name "MANUFACTURER PART NUMBER") "RC1206FR-0720RL")
        (field (name "MANUFACTURER") "Yageo")
      )
      (libsource (lib "VESC_MotorController") (part "20ohm 0.25W ±1%"))
    )
    (comp (ref "R16")
      (value "20R")
      (footprint "R1206")
      (description "20 ohm 0.25W ±1%")
      (fields
        (field (name "MANUFACTURER PART NUMBER") "RC1206FR-0720RL")
        (field (name "MANUFACTURER") "Yageo")
      )
      (libsource (lib "VESC_MotorController") (part "20ohm 0.25W ±1%"))
    )
    (comp (ref "R17")
      (value "1k")
      (footprint "R0603")
      (description "1 kOhms ±1% 0.1W")
      (fields
        (field (name "MANUFACTURER") "Yageo")
        (field (name "MANUFACTURER PART NUMBER") "RC0603FR-071KL")
      )
      (libsource (lib "VESC_MotorController") (part "1 kOhms ±1% 0.1W"))
    )
    (comp (ref "R18")
      (value "39k")
      (footprint "R0805")
      (description "39 kOhms ±1% 0.8W")
      (fields
        (field (name "MANUFACTURER") "Yageo")
        (field (name "MANUFACTURER PART NUMBER") "RT0805FRE0739KL")
      )
      (libsource (lib "VESC_MotorController") (part "39 kOhms ±1% 0.8W"))
    )
    (comp (ref "R19")
      (value "10k")
      (footprint "R0603")
      (description "10 kOhms ±1% 0.1W")
      (fields
        (field (name "MANUFACTURER") "Yageo")
        (field (name "MANUFACTURER PART NUMBER") "RC0603FR-0710KL")
      )
      (libsource (lib "VESC_MotorController") (part "10 kOhms ±1% 0.1W"))
    )
    (comp (ref "R20")
      (value "2.2k")
      (footprint "R0805")
      (description "2.2 kOhms ±1% 0.8W")
      (fields
        (field (name "MANUFACTURER") "Yageo")
        (field (name "MANUFACTURER PART NUMBER") "RT0805FRE072K2L")
      )
      (libsource (lib "VESC_MotorController") (part "2.2 kOhms ±1% 0.8W"))
    )
    (comp (ref "R21")
      (value "20R")
      (footprint "R1206")
      (description "20 ohm 0.25W ±1%")
      (fields
        (field (name "MANUFACTURER PART NUMBER") "RC1206FR-0720RL")
        (field (name "MANUFACTURER") "Yageo")
      )
      (libsource (lib "VESC_MotorController") (part "20 ohm 0.25W ±1%"))
    )
    (comp (ref "R22")
      (value "4.7R")
      (footprint "R1206")
      (description "4.7 ohm 0.25W ±1%")
      (fields
        (field (name "MANUFACTURER PART NUMBER") "RC1206FR-074R7L")
        (field (name "MANUFACTURER") "Yageo")
      )
      (libsource (lib "VESC_MotorController") (part "4.7 ohm 0.25W ±1%"))
    )
    (comp (ref "R23")
      (value "10k")
      (footprint "R0603")
      (description "10 kOhms ±1% 0.1W")
      (fields
        (field (name "MANUFACTURER") "Yageo")
        (field (name "MANUFACTURER PART NUMBER") "RC0603FR-0710KL")
      )
      (libsource (lib "VESC_MotorController") (part "10 kOhms ±1% 0.1W"))
    )
    (comp (ref "R24")
      (value "2.2R")
      (footprint "R1206")
      (description "2.2 ohm 0.25W ±1%")
      (fields
        (field (name "MANUFACTURER PART NUMBER") "RC1206FR-072R2L")
        (field (name "MANUFACTURER") "Yageo")
      )
      (libsource (lib "VESC_MotorController") (part "2.2ohm 0.25W ±1%"))
    )
    (comp (ref "R25")
      (value "0.5mR/9W")
      (footprint "RESC10052X137N")
      (description "Current Sense Resistors - SMD 0.5mOHMS 9W 1% AEC-Q200")
      (fields
        (field (name "MANUFACTURER") "Bourns")
        (field (name "MANUFACTURER PART NUMBER") "CSS2H-3920R-L500FE")
      )
      (libsource (lib "VESC_MotorController") (part "CSS2H-3920R-L500FE"))
    )
    (comp (ref "R26")
      (value "0.5mR/9W")
      (footprint "RESC10052X137N")
      (description "Current Sense Resistors - SMD 0.5mOHMS 9W 1% AEC-Q200")
      (fields
        (field (name "MANUFACTURER") "Bourns")
        (field (name "MANUFACTURER PART NUMBER") "CSS2H-3920R-L500FE")
      )
      (libsource (lib "VESC_MotorController") (part "CSS2H-3920R-L500FE"))
    )
    (comp (ref "R27")
      (value "4.7R")
      (footprint "R1206")
      (description "4.7 ohm 0.25W ±1%")
      (fields
        (field (name "MANUFACTURER PART NUMBER") "RC1206FR-074R7L")
        (field (name "MANUFACTURER") "Yageo")
      )
      (libsource (lib "VESC_MotorController") (part "4.7 ohm 0.25W ±1%"))
    )
    (comp (ref "R28")
      (value "0.5mR/9W")
      (footprint "RESC10052X137N")
      (description "Current Sense Resistors - SMD 0.5mOHMS 9W 1% AEC-Q200")
      (fields
        (field (name "MANUFACTURER") "Bourns")
        (field (name "MANUFACTURER PART NUMBER") "CSS2H-3920R-L500FE")
      )
      (libsource (lib "VESC_MotorController") (part "CSS2H-3920R-L500FE"))
    )
    (comp (ref "R29")
      (value "20R")
      (footprint "R1206")
      (description "20 ohm 0.25W ±1%")
      (fields
        (field (name "MANUFACTURER PART NUMBER") "RC1206FR-0720RL")
        (field (name "MANUFACTURER") "Yageo")
      )
      (libsource (lib "VESC_MotorController") (part "20 ohm 0.25W ±1%"))
    )
    (comp (ref "R30")
      (value "2.2k")
      (footprint "R0603")
      (description "2.2 kOhms ±1% 0.1W")
      (fields
        (field (name "MANUFACTURER") "Yageo")
        (field (name "MANUFACTURER PART NUMBER") "RC0603FR-072K2L")
      )
      (libsource (lib "VESC_MotorController") (part "2.2 kOhms ±1% 0.1W"))
    )
    (comp (ref "R31")
      (value "2.2k")
      (footprint "R0603")
      (description "2.2 kOhms ±1% 0.1W")
      (fields
        (field (name "MANUFACTURER") "Yageo")
        (field (name "MANUFACTURER PART NUMBER") "RC0603FR-072K2L")
      )
      (libsource (lib "VESC_MotorController") (part "2.2 kOhms ±1% 0.1W"))
    )
    (comp (ref "R32")
      (value "2.2k")
      (footprint "R0603")
      (description "2.2 kOhms ±1% 0.1W")
      (fields
        (field (name "MANUFACTURER") "Yageo")
        (field (name "MANUFACTURER PART NUMBER") "RC0603FR-072K2L")
      )
      (libsource (lib "VESC_MotorController") (part "2.2 kOhms ±1% 0.1W"))
    )
    (comp (ref "R33")
      (value "0.5mR/9W")
      (footprint "RESC10052X137N")
      (description "Current Sense Resistors - SMD 0.5mOHMS 9W 1% AEC-Q200")
      (fields
        (field (name "MANUFACTURER") "Bourns")
        (field (name "MANUFACTURER PART NUMBER") "CSS2H-3920R-L500FE")
      )
      (libsource (lib "VESC_MotorController") (part "CSS2H-3920R-L500FE"))
    )
    (comp (ref "R34")
      (value "20R")
      (footprint "R1206")
      (description "20 ohm 0.25W ±1%")
      (fields
        (field (name "MANUFACTURER PART NUMBER") "RC1206FR-0720RL")
        (field (name "MANUFACTURER") "Yageo")
      )
      (libsource (lib "VESC_MotorController") (part "20ohm 0.25W ±1%"))
    )
    (comp (ref "R35")
      (value "0.5mR/9W")
      (footprint "RESC10052X137N")
      (description "Current Sense Resistors - SMD 0.5mOHMS 9W 1% AEC-Q200")
      (fields
        (field (name "MANUFACTURER") "Bourns")
        (field (name "MANUFACTURER PART NUMBER") "CSS2H-3920R-L500FE")
      )
      (libsource (lib "VESC_MotorController") (part "CSS2H-3920R-L500FE"))
    )
    (comp (ref "R36")
      (value "20R")
      (footprint "R1206")
      (description "20 ohm 0.25W ±1%")
      (fields
        (field (name "MANUFACTURER PART NUMBER") "RC1206FR-0720RL")
        (field (name "MANUFACTURER") "Yageo")
      )
      (libsource (lib "VESC_MotorController") (part "20ohm 0.25W ±1%"))
    )
    (comp (ref "R37")
      (value "20R")
      (footprint "R1206")
      (description "20 ohm 0.25W ±1%")
      (fields
        (field (name "MANUFACTURER PART NUMBER") "RC1206FR-0720RL")
        (field (name "MANUFACTURER") "Yageo")
      )
      (libsource (lib "VESC_MotorController") (part "20ohm 0.25W ±1%"))
    )
    (comp (ref "R38")
      (value "1k")
      (footprint "R0603")
      (description "1 kOhms ±1% 0.1W")
      (fields
        (field (name "MANUFACTURER") "Yageo")
        (field (name "MANUFACTURER PART NUMBER") "RC0603FR-071KL")
      )
      (libsource (lib "VESC_MotorController") (part "1 kOhms ±1% 0.1W"))
    )
    (comp (ref "R39")
      (value "39k")
      (footprint "R0805")
      (description "39 kOhms ±1% 0.8W")
      (fields
        (field (name "MANUFACTURER") "Yageo")
        (field (name "MANUFACTURER PART NUMBER") "RT0805FRE0739KL")
      )
      (libsource (lib "VESC_MotorController") (part "39 kOhms ±1% 0.8W"))
    )
    (comp (ref "R40")
      (value "10k")
      (footprint "R0603")
      (description "10 kOhms ±1% 0.1W")
      (fields
        (field (name "MANUFACTURER") "Yageo")
        (field (name "MANUFACTURER PART NUMBER") "RC0603FR-0710KL")
      )
      (libsource (lib "VESC_MotorController") (part "10 kOhms ±1% 0.1W"))
    )
    (comp (ref "R41")
      (value "2.2k")
      (footprint "R0805")
      (description "2.2 kOhms ±1% 0.8W")
      (fields
        (field (name "MANUFACTURER") "Yageo")
        (field (name "MANUFACTURER PART NUMBER") "RT0805FRE072K2L")
      )
      (libsource (lib "VESC_MotorController") (part "2.2 kOhms ±1% 0.8W"))
    )
    (comp (ref "R42")
      (value "20R")
      (footprint "R1206")
      (description "20 ohm 0.25W ±1%")
      (fields
        (field (name "MANUFACTURER PART NUMBER") "RC1206FR-0720RL")
        (field (name "MANUFACTURER") "Yageo")
      )
      (libsource (lib "VESC_MotorController") (part "20 ohm 0.25W ±1%"))
    )
    (comp (ref "R43")
      (value "10k")
      (footprint "R0603")
      (description "10 kOhms ±1% 0.1W")
      (fields
        (field (name "MANUFACTURER") "Yageo")
        (field (name "MANUFACTURER PART NUMBER") "RC0603FR-0710KL")
      )
      (libsource (lib "VESC_MotorController") (part "10 kOhms ±1% 0.1W"))
    )
    (comp (ref "R44")
      (value "4.7R")
      (footprint "R1206")
      (description "4.7 ohm 0.25W ±1%")
      (fields
        (field (name "MANUFACTURER PART NUMBER") "RC1206FR-074R7L")
        (field (name "MANUFACTURER") "Yageo")
      )
      (libsource (lib "VESC_MotorController") (part "4.7 ohm 0.25W ±1%"))
    )
    (comp (ref "R45")
      (value "2.2R")
      (footprint "R1206")
      (description "2.2 ohm 0.25W ±1%")
      (fields
        (field (name "MANUFACTURER PART NUMBER") "RC1206FR-072R2L")
        (field (name "MANUFACTURER") "Yageo")
      )
      (libsource (lib "VESC_MotorController") (part "2.2ohm 0.25W ±1%"))
    )
    (comp (ref "R46")
      (value "0.5mR/9W")
      (footprint "RESC10052X137N")
      (description "Current Sense Resistors - SMD 0.5mOHMS 9W 1% AEC-Q200")
      (fields
        (field (name "MANUFACTURER") "Bourns")
        (field (name "MANUFACTURER PART NUMBER") "CSS2H-3920R-L500FE")
      )
      (libsource (lib "VESC_MotorController") (part "CSS2H-3920R-L500FE"))
    )
    (comp (ref "R47")
      (value "0.5mR/9W")
      (footprint "RESC10052X137N")
      (description "Current Sense Resistors - SMD 0.5mOHMS 9W 1% AEC-Q200")
      (fields
        (field (name "MANUFACTURER") "Bourns")
        (field (name "MANUFACTURER PART NUMBER") "CSS2H-3920R-L500FE")
      )
      (libsource (lib "VESC_MotorController") (part "CSS2H-3920R-L500FE"))
    )
    (comp (ref "R48")
      (value "4.7R")
      (footprint "R1206")
      (description "4.7 ohm 0.25W ±1%")
      (fields
        (field (name "MANUFACTURER PART NUMBER") "RC1206FR-074R7L")
        (field (name "MANUFACTURER") "Yageo")
      )
      (libsource (lib "VESC_MotorController") (part "4.7 ohm 0.25W ±1%"))
    )
    (comp (ref "R49")
      (value "0.5mR/9W")
      (footprint "RESC10052X137N")
      (description "Current Sense Resistors - SMD 0.5mOHMS 9W 1% AEC-Q200")
      (fields
        (field (name "MANUFACTURER") "Bourns")
        (field (name "MANUFACTURER PART NUMBER") "CSS2H-3920R-L500FE")
      )
      (libsource (lib "VESC_MotorController") (part "CSS2H-3920R-L500FE"))
    )
    (comp (ref "R50")
      (value "20R")
      (footprint "R1206")
      (description "20 ohm 0.25W ±1%")
      (fields
        (field (name "MANUFACTURER PART NUMBER") "RC1206FR-0720RL")
        (field (name "MANUFACTURER") "Yageo")
      )
      (libsource (lib "VESC_MotorController") (part "20 ohm 0.25W ±1%"))
    )
    (comp (ref "R51")
      (value "2.2k")
      (footprint "R0603")
      (description "2.2 kOhms ±1% 0.1W")
      (fields
        (field (name "MANUFACTURER") "Yageo")
        (field (name "MANUFACTURER PART NUMBER") "RC0603FR-072K2L")
      )
      (libsource (lib "VESC_MotorController") (part "2.2 kOhms ±1% 0.1W"))
    )
    (comp (ref "R52")
      (value "2.2k")
      (footprint "R0603")
      (description "2.2 kOhms ±1% 0.1W")
      (fields
        (field (name "MANUFACTURER") "Yageo")
        (field (name "MANUFACTURER PART NUMBER") "RC0603FR-072K2L")
      )
      (libsource (lib "VESC_MotorController") (part "2.2 kOhms ±1% 0.1W"))
    )
    (comp (ref "R53")
      (value "2.2k")
      (footprint "R0603")
      (description "2.2 kOhms ±1% 0.1W")
      (fields
        (field (name "MANUFACTURER") "Yageo")
        (field (name "MANUFACTURER PART NUMBER") "RC0603FR-072K2L")
      )
      (libsource (lib "VESC_MotorController") (part "2.2 kOhms ±1% 0.1W"))
    )
    (comp (ref "R54")
      (value "0.5mR/9W")
      (footprint "RESC10052X137N")
      (description "Current Sense Resistors - SMD 0.5mOHMS 9W 1% AEC-Q200")
      (fields
        (field (name "MANUFACTURER") "Bourns")
        (field (name "MANUFACTURER PART NUMBER") "CSS2H-3920R-L500FE")
      )
      (libsource (lib "VESC_MotorController") (part "CSS2H-3920R-L500FE"))
    )
    (comp (ref "R55")
      (value "20R")
      (footprint "R1206")
      (description "20 ohm 0.25W ±1%")
      (fields
        (field (name "MANUFACTURER PART NUMBER") "RC1206FR-0720RL")
        (field (name "MANUFACTURER") "Yageo")
      )
      (libsource (lib "VESC_MotorController") (part "20ohm 0.25W ±1%"))
    )
    (comp (ref "R56")
      (value "0.5mR/9W")
      (footprint "RESC10052X137N")
      (description "Current Sense Resistors - SMD 0.5mOHMS 9W 1% AEC-Q200")
      (fields
        (field (name "MANUFACTURER") "Bourns")
        (field (name "MANUFACTURER PART NUMBER") "CSS2H-3920R-L500FE")
      )
      (libsource (lib "VESC_MotorController") (part "CSS2H-3920R-L500FE"))
    )
    (comp (ref "R57")
      (value "20R")
      (footprint "R1206")
      (description "20 ohm 0.25W ±1%")
      (fields
        (field (name "MANUFACTURER PART NUMBER") "RC1206FR-0720RL")
        (field (name "MANUFACTURER") "Yageo")
      )
      (libsource (lib "VESC_MotorController") (part "20ohm 0.25W ±1%"))
    )
    (comp (ref "R58")
      (value "20R")
      (footprint "R1206")
      (description "20 ohm 0.25W ±1%")
      (fields
        (field (name "MANUFACTURER PART NUMBER") "RC1206FR-0720RL")
        (field (name "MANUFACTURER") "Yageo")
      )
      (libsource (lib "VESC_MotorController") (part "20ohm 0.25W ±1%"))
    )
    (comp (ref "R59")
      (value "1k")
      (footprint "R0603")
      (description "1 kOhms ±1% 0.1W")
      (fields
        (field (name "MANUFACTURER") "Yageo")
        (field (name "MANUFACTURER PART NUMBER") "RC0603FR-071KL")
      )
      (libsource (lib "VESC_MotorController") (part "1 kOhms ±1% 0.1W"))
    )
    (comp (ref "R60")
      (value "39k")
      (footprint "R0805")
      (description "39 kOhms ±1% 0.8W")
      (fields
        (field (name "MANUFACTURER") "Yageo")
        (field (name "MANUFACTURER PART NUMBER") "RT0805FRE0739KL")
      )
      (libsource (lib "VESC_MotorController") (part "39 kOhms ±1% 0.8W"))
    )
    (comp (ref "R61")
      (value "10k")
      (footprint "R0603")
      (description "10 kOhms ±1% 0.1W")
      (fields
        (field (name "MANUFACTURER") "Yageo")
        (field (name "MANUFACTURER PART NUMBER") "RC0603FR-0710KL")
      )
      (libsource (lib "VESC_MotorController") (part "10 kOhms ±1% 0.1W"))
    )
    (comp (ref "R62")
      (value "2.2k")
      (footprint "R0805")
      (description "2.2 kOhms ±1% 0.8W")
      (fields
        (field (name "MANUFACTURER") "Yageo")
        (field (name "MANUFACTURER PART NUMBER") "RT0805FRE072K2L")
      )
      (libsource (lib "VESC_MotorController") (part "2.2 kOhms ±1% 0.8W"))
    )
    (comp (ref "R63")
      (value "20R")
      (footprint "R1206")
      (description "20 ohm 0.25W ±1%")
      (fields
        (field (name "MANUFACTURER PART NUMBER") "RC1206FR-0720RL")
        (field (name "MANUFACTURER") "Yageo")
      )
      (libsource (lib "VESC_MotorController") (part "20 ohm 0.25W ±1%"))
    )
    (comp (ref "R64")
      (value "10k")
      (footprint "R0603")
      (description "10 kOhms ±1% 0.1W")
      (fields
        (field (name "MANUFACTURER") "Yageo")
        (field (name "MANUFACTURER PART NUMBER") "RC0603FR-0710KL")
      )
      (libsource (lib "VESC_MotorController") (part "10 kOhms ±1% 0.1W"))
    )
    (comp (ref "R65")
      (value "4.7R")
      (footprint "R1206")
      (description "4.7 ohm 0.25W ±1%")
      (fields
        (field (name "MANUFACTURER PART NUMBER") "RC1206FR-074R7L")
        (field (name "MANUFACTURER") "Yageo")
      )
      (libsource (lib "VESC_MotorController") (part "4.7 ohm 0.25W ±1%"))
    )
    (comp (ref "U1")
      (value "UCC21520ADW")
      (footprint "SOIC127P1030X265-16N")
      (description "4A/6A, 5.7 kVrms Isolated Dual Channel Gate Driver")
      (fields (field (name "MANUFACTURER") "Texas Instruments"))
      (libsource (lib "VESC_MotorController") (part "UCC21520ADW"))
    )
    (comp (ref "U2")
      (value "INA240A2QDRQ1")
      (footprint "SOIC127P600X175-8N")
      (description "Automotive, High/Low Side, Bi-Directional Zer-Drift Current Sense Amp w/ Enhanced PWM Rejection")
      (fields (field (name "MANUFACTURER") "Texas Instruments"))
      (libsource (lib "VESC_MotorController") (part "INA240A2QDRQ1"))
    )
    (comp (ref "U3")
      (value "UCC21520ADW")
      (footprint "SOIC127P1030X265-16N")
      (description "4A/6A, 5.7 kVrms Isolated Dual Channel Gate Driver")
      (fields (field (name "MANUFACTURER") "Texas Instruments"))
      (libsource (lib "VESC_MotorController") (part "UCC21520ADW"))
    )
    (comp (ref "U4")
      (value "INA240A2QDRQ1")
      (footprint "SOIC127P600X175-8N")
      (description "Automotive, High/Low Side, Bi-Directional Zer-Drift Current Sense Amp w/ Enhanced PWM Rejection")
      (fields (field (name "MANUFACTURER") "Texas Instruments"))
      (libsource (lib "VESC_MotorController") (part "INA240A2QDRQ1"))
    )
    (comp (ref "U5")
      (value "UCC21520ADW")
      (footprint "SOIC127P1030X265-16N")
      (description "4A/6A, 5.7 kVrms Isolated Dual Channel Gate Driver")
      (fields (field (name "MANUFACTURER") "Texas Instruments"))
      (libsource (lib "VESC_MotorController") (part "UCC21520ADW"))
    )
    (comp (ref "U6")
      (value "INA240A2QDRQ1")
      (footprint "SOIC127P600X175-8N")
      (description "Automotive, High/Low Side, Bi-Directional Zer-Drift Current Sense Amp w/ Enhanced PWM Rejection")
      (fields (field (name "MANUFACTURER") "Texas Instruments"))
      (libsource (lib "VESC_MotorController") (part "INA240A2QDRQ1"))
    )
  )
  (nets
    (net (code "1") (name "+3V3") (class "Default")
      (node (ref "B1") (pin "1") (pinfunction "1_1") (pintype "passive"))
      (node (ref "B2") (pin "1") (pinfunction "1_1") (pintype "passive"))
      (node (ref "B3") (pin "1") (pinfunction "1_1") (pintype "passive"))
      (node (ref "C13") (pin "2") (pinfunction "2_2") (pintype "passive"))
      (node (ref "C14") (pin "2") (pinfunction "2_2") (pintype "passive"))
      (node (ref "C17") (pin "2") (pinfunction "2_2") (pintype "passive"))
      (node (ref "C32") (pin "2") (pinfunction "2_2") (pintype "passive"))
      (node (ref "C33") (pin "2") (pinfunction "2_2") (pintype "passive"))
      (node (ref "C36") (pin "2") (pinfunction "2_2") (pintype "passive"))
      (node (ref "C56") (pin "2") (pinfunction "2_2") (pintype "passive"))
      (node (ref "C57") (pin "2") (pinfunction "2_2") (pintype "passive"))
      (node (ref "C60") (pin "2") (pinfunction "2_2") (pintype "passive"))
      (node (ref "J8") (pin "3") (pinfunction "3_3") (pintype "passive"))
      (node (ref "J8") (pin "4") (pinfunction "4_4") (pintype "passive"))
      (node (ref "U1") (pin "3") (pinfunction "VCCI_1_3") (pintype "passive"))
      (node (ref "U1") (pin "8") (pinfunction "VCCI_2_8") (pintype "passive"))
      (node (ref "U2") (pin "3") (pinfunction "REF2_3") (pintype "passive"))
      (node (ref "U2") (pin "6") (pinfunction "VS_6") (pintype "passive"))
      (node (ref "U3") (pin "3") (pinfunction "VCCI_1_3") (pintype "passive"))
      (node (ref "U3") (pin "8") (pinfunction "VCCI_2_8") (pintype "passive"))
      (node (ref "U4") (pin "3") (pinfunction "REF2_3") (pintype "passive"))
      (node (ref "U4") (pin "6") (pinfunction "VS_6") (pintype "passive"))
      (node (ref "U5") (pin "3") (pinfunction "VCCI_1_3") (pintype "passive"))
      (node (ref "U5") (pin "8") (pinfunction "VCCI_2_8") (pintype "passive"))
      (node (ref "U6") (pin "3") (pinfunction "REF2_3") (pintype "passive"))
      (node (ref "U6") (pin "6") (pinfunction "VS_6") (pintype "passive"))
    )
    (net (code "2") (name "+12V") (class "Default")
      (node (ref "C15") (pin "2") (pinfunction "2_2") (pintype "passive"))
      (node (ref "C16") (pin "2") (pinfunction "2_2") (pintype "passive"))
      (node (ref "C34") (pin "2") (pinfunction "2_2") (pintype "passive"))
      (node (ref "C35") (pin "2") (pinfunction "2_2") (pintype "passive"))
      (node (ref "C58") (pin "2") (pinfunction "2_2") (pintype "passive"))
      (node (ref "C59") (pin "2") (pinfunction "2_2") (pintype "passive"))
      (node (ref "J8") (pin "1") (pinfunction "1_1") (pintype "passive"))
      (node (ref "J8") (pin "2") (pinfunction "2_2") (pintype "passive"))
      (node (ref "R1") (pin "1") (pinfunction "1_1") (pintype "passive"))
      (node (ref "R24") (pin "1") (pinfunction "1_1") (pintype "passive"))
      (node (ref "R45") (pin "1") (pinfunction "1_1") (pintype "passive"))
      (node (ref "U1") (pin "11") (pinfunction "VDDB_11") (pintype "passive"))
      (node (ref "U3") (pin "11") (pinfunction "VDDB_11") (pintype "passive"))
      (node (ref "U5") (pin "11") (pinfunction "VDDB_11") (pintype "passive"))
    )
    (net (code "3") (name "/DISABLE") (class "Default")
      (node (ref "J1") (pin "6") (pinfunction "6_6") (pintype "passive"))
      (node (ref "J4") (pin "6") (pinfunction "6_6") (pintype "passive"))
      (node (ref "J9") (pin "6") (pinfunction "6_6") (pintype "passive"))
      (node (ref "R16") (pin "1") (pinfunction "1_1") (pintype "passive"))
      (node (ref "R37") (pin "1") (pinfunction "1_1") (pintype "passive"))
      (node (ref "R58") (pin "1") (pinfunction "1_1") (pintype "passive"))
    )
    (net (code "4") (name "/ISENSE_U") (class "Default")
      (node (ref "J1") (pin "3") (pinfunction "3_3") (pintype "passive"))
      (node (ref "R17") (pin "2") (pinfunction "2_2") (pintype "passive"))
    )
    (net (code "5") (name "/ISENSE_V") (class "Default")
      (node (ref "J4") (pin "3") (pinfunction "3_3") (pintype "passive"))
      (node (ref "R38") (pin "2") (pinfunction "2_2") (pintype "passive"))
    )
    (net (code "6") (name "/ISENSE_W") (class "Default")
      (node (ref "J9") (pin "3") (pinfunction "3_3") (pintype "passive"))
      (node (ref "R59") (pin "2") (pinfunction "2_2") (pintype "passive"))
    )
    (net (code "7") (name "/OUT_U") (class "Default")
      (node (ref "J5") (pin "1") (pinfunction "1_1") (pintype "passive"))
      (node (ref "R11") (pin "1") (pinfunction "1_1") (pintype "passive"))
      (node (ref "R14") (pin "1") (pinfunction "1_1") (pintype "passive"))
      (node (ref "R2") (pin "1") (pinfunction "1_1") (pintype "passive"))
      (node (ref "R3") (pin "1") (pinfunction "1_1") (pintype "passive"))
      (node (ref "R6") (pin "1") (pinfunction "1_1") (pintype "passive"))
      (node (ref "U2") (pin "1") (pinfunction "IN-_1") (pintype "passive"))
    )
    (net (code "8") (name "/OUT_V") (class "Default")
      (node (ref "J6") (pin "1") (pinfunction "1_1") (pintype "passive"))
      (node (ref "R25") (pin "1") (pinfunction "1_1") (pintype "passive"))
      (node (ref "R26") (pin "1") (pinfunction "1_1") (pintype "passive"))
      (node (ref "R28") (pin "1") (pinfunction "1_1") (pintype "passive"))
      (node (ref "R33") (pin "1") (pinfunction "1_1") (pintype "passive"))
      (node (ref "R35") (pin "1") (pinfunction "1_1") (pintype "passive"))
      (node (ref "U4") (pin "1") (pinfunction "IN-_1") (pintype "passive"))
    )
    (net (code "9") (name "/OUT_W") (class "Default")
      (node (ref "J7") (pin "1") (pinfunction "1_1") (pintype "passive"))
      (node (ref "R46") (pin "1") (pinfunction "1_1") (pintype "passive"))
      (node (ref "R47") (pin "1") (pinfunction "1_1") (pintype "passive"))
      (node (ref "R49") (pin "1") (pinfunction "1_1") (pintype "passive"))
      (node (ref "R54") (pin "1") (pinfunction "1_1") (pintype "passive"))
      (node (ref "R56") (pin "1") (pinfunction "1_1") (pintype "passive"))
      (node (ref "U6") (pin "1") (pinfunction "IN-_1") (pintype "passive"))
    )
    (net (code "10") (name "/PHASE_U") (class "Default")
      (node (ref "C1") (pin "1") (pinfunction "1_1") (pintype "passive"))
      (node (ref "C2") (pin "1") (pinfunction "1_1") (pintype "passive"))
      (node (ref "Q1") (pin "SOURCE") (pinfunction "SOURCE_SOURCE") (pintype "passive"))
      (node (ref "Q2") (pin "SOURCE") (pinfunction "SOURCE_SOURCE") (pintype "passive"))
      (node (ref "Q3") (pin "SOURCE") (pinfunction "SOURCE_SOURCE") (pintype "passive"))
      (node (ref "Q4") (pin "SOURCE") (pinfunction "SOURCE_SOURCE") (pintype "passive"))
      (node (ref "Q5") (pin "DRAIN") (pinfunction "DRAIN_DRAIN") (pintype "passive"))
      (node (ref "Q6") (pin "DRAIN") (pinfunction "DRAIN_DRAIN") (pintype "passive"))
      (node (ref "Q7") (pin "DRAIN") (pinfunction "DRAIN_DRAIN") (pintype "passive"))
      (node (ref "Q8") (pin "DRAIN") (pinfunction "DRAIN_DRAIN") (pintype "passive"))
      (node (ref "R11") (pin "2") (pinfunction "2_2") (pintype "passive"))
      (node (ref "R14") (pin "2") (pinfunction "2_2") (pintype "passive"))
      (node (ref "R18") (pin "2") (pinfunction "2_2") (pintype "passive"))
      (node (ref "R2") (pin "2") (pinfunction "2_2") (pintype "passive"))
      (node (ref "R3") (pin "2") (pinfunction "2_2") (pintype "passive"))
      (node (ref "R6") (pin "2") (pinfunction "2_2") (pintype "passive"))
      (node (ref "U1") (pin "14") (pinfunction "VSSA_14") (pintype "passive"))
      (node (ref "U2") (pin "8") (pinfunction "IN+_8") (pintype "passive"))
    )
    (net (code "11") (name "/PHASE_V") (class "Default")
      (node (ref "C19") (pin "1") (pinfunction "1_1") (pintype "passive"))
      (node (ref "C20") (pin "1") (pinfunction "1_1") (pintype "passive"))
      (node (ref "Q10") (pin "SOURCE") (pinfunction "SOURCE_SOURCE") (pintype "passive"))
      (node (ref "Q11") (pin "SOURCE") (pinfunction "SOURCE_SOURCE") (pintype "passive"))
      (node (ref "Q12") (pin "SOURCE") (pinfunction "SOURCE_SOURCE") (pintype "passive"))
      (node (ref "Q13") (pin "DRAIN") (pinfunction "DRAIN_DRAIN") (pintype "passive"))
      (node (ref "Q14") (pin "DRAIN") (pinfunction "DRAIN_DRAIN") (pintype "passive"))
      (node (ref "Q15") (pin "DRAIN") (pinfunction "DRAIN_DRAIN") (pintype "passive"))
      (node (ref "Q16") (pin "DRAIN") (pinfunction "DRAIN_DRAIN") (pintype "passive"))
      (node (ref "Q9") (pin "SOURCE") (pinfunction "SOURCE_SOURCE") (pintype "passive"))
      (node (ref "R25") (pin "2") (pinfunction "2_2") (pintype "passive"))
      (node (ref "R26") (pin "2") (pinfunction "2_2") (pintype "passive"))
      (node (ref "R28") (pin "2") (pinfunction "2_2") (pintype "passive"))
      (node (ref "R33") (pin "2") (pinfunction "2_2") (pintype "passive"))
      (node (ref "R35") (pin "2") (pinfunction "2_2") (pintype "passive"))
      (node (ref "R39") (pin "2") (pinfunction "2_2") (pintype "passive"))
      (node (ref "U3") (pin "14") (pinfunction "VSSA_14") (pintype "passive"))
      (node (ref "U4") (pin "8") (pinfunction "IN+_8") (pintype "passive"))
    )
    (net (code "12") (name "/PHASE_W") (class "Default")
      (node (ref "C39") (pin "1") (pinfunction "1_1") (pintype "passive"))
      (node (ref "C40") (pin "1") (pinfunction "1_1") (pintype "passive"))
      (node (ref "Q17") (pin "SOURCE") (pinfunction "SOURCE_SOURCE") (pintype "passive"))
      (node (ref "Q18") (pin "SOURCE") (pinfunction "SOURCE_SOURCE") (pintype "passive"))
      (node (ref "Q19") (pin "SOURCE") (pinfunction "SOURCE_SOURCE") (pintype "passive"))
      (node (ref "Q20") (pin "SOURCE") (pinfunction "SOURCE_SOURCE") (pintype "passive"))
      (node (ref "Q21") (pin "DRAIN") (pinfunction "DRAIN_DRAIN") (pintype "passive"))
      (node (ref "Q22") (pin "DRAIN") (pinfunction "DRAIN_DRAIN") (pintype "passive"))
      (node (ref "Q23") (pin "DRAIN") (pinfunction "DRAIN_DRAIN") (pintype "passive"))
      (node (ref "Q24") (pin "DRAIN") (pinfunction "DRAIN_DRAIN") (pintype "passive"))
      (node (ref "R46") (pin "2") (pinfunction "2_2") (pintype "passive"))
      (node (ref "R47") (pin "2") (pinfunction "2_2") (pintype "passive"))
      (node (ref "R49") (pin "2") (pinfunction "2_2") (pintype "passive"))
      (node (ref "R54") (pin "2") (pinfunction "2_2") (pintype "passive"))
      (node (ref "R56") (pin "2") (pinfunction "2_2") (pintype "passive"))
      (node (ref "R60") (pin "2") (pinfunction "2_2") (pintype "passive"))
      (node (ref "U5") (pin "14") (pinfunction "VSSA_14") (pintype "passive"))
      (node (ref "U6") (pin "8") (pinfunction "IN+_8") (pintype "passive"))
    )
    (net (code "13") (name "/PWM_U_HIGH") (class "Default")
      (node (ref "J1") (pin "2") (pinfunction "2_2") (pintype "passive"))
      (node (ref "R13") (pin "1") (pinfunction "1_1") (pintype "passive"))
    )
    (net (code "14") (name "/PWM_U_LOW") (class "Default")
      (node (ref "J1") (pin "4") (pinfunction "4_4") (pintype "passive"))
      (node (ref "R15") (pin "1") (pinfunction "1_1") (pintype "passive"))
    )
    (net (code "15") (name "/PWM_V_HIGH") (class "Default")
      (node (ref "J4") (pin "2") (pinfunction "2_2") (pintype "passive"))
      (node (ref "R34") (pin "1") (pinfunction "1_1") (pintype "passive"))
    )
    (net (code "16") (name "/PWM_V_LOW") (class "Default")
      (node (ref "J4") (pin "4") (pinfunction "4_4") (pintype "passive"))
      (node (ref "R36") (pin "1") (pinfunction "1_1") (pintype "passive"))
    )
    (net (code "17") (name "/PWM_W_HIGH") (class "Default")
      (node (ref "J9") (pin "2") (pinfunction "2_2") (pintype "passive"))
      (node (ref "R55") (pin "1") (pinfunction "1_1") (pintype "passive"))
    )
    (net (code "18") (name "/PWM_W_LOW") (class "Default")
      (node (ref "J9") (pin "4") (pinfunction "4_4") (pintype "passive"))
      (node (ref "R57") (pin "1") (pinfunction "1_1") (pintype "passive"))
    )
    (net (code "19") (name "/TEMP_U") (class "Default")
      (node (ref "B1") (pin "2") (pinfunction "2_2") (pintype "passive"))
      (node (ref "C18") (pin "2") (pinfunction "2_2") (pintype "passive"))
      (node (ref "J1") (pin "5") (pinfunction "5_5") (pintype "passive"))
      (node (ref "R23") (pin "2") (pinfunction "2_2") (pintype "passive"))
    )
    (net (code "20") (name "/TEMP_V") (class "Default")
      (node (ref "B2") (pin "2") (pinfunction "2_2") (pintype "passive"))
      (node (ref "C31") (pin "2") (pinfunction "2_2") (pintype "passive"))
      (node (ref "J4") (pin "5") (pinfunction "5_5") (pintype "passive"))
      (node (ref "R43") (pin "2") (pinfunction "2_2") (pintype "passive"))
    )
    (net (code "21") (name "/TEMP_W") (class "Default")
      (node (ref "B3") (pin "2") (pinfunction "2_2") (pintype "passive"))
      (node (ref "C55") (pin "2") (pinfunction "2_2") (pintype "passive"))
      (node (ref "J9") (pin "5") (pinfunction "5_5") (pintype "passive"))
      (node (ref "R64") (pin "2") (pinfunction "2_2") (pintype "passive"))
    )
    (net (code "22") (name "/VSENSE") (class "Default")
      (node (ref "J8") (pin "6") (pinfunction "6_6") (pintype "passive"))
      (node (ref "R12") (pin "2") (pinfunction "2_2") (pintype "passive"))
      (node (ref "R4") (pin "1") (pinfunction "1_1") (pintype "passive"))
    )
    (net (code "23") (name "/VSENSE_U") (class "Default")
      (node (ref "J1") (pin "1") (pinfunction "1_1") (pintype "passive"))
      (node (ref "R18") (pin "1") (pinfunction "1_1") (pintype "passive"))
      (node (ref "R20") (pin "2") (pinfunction "2_2") (pintype "passive"))
    )
    (net (code "24") (name "/VSENSE_V") (class "Default")
      (node (ref "J4") (pin "1") (pinfunction "1_1") (pintype "passive"))
      (node (ref "R39") (pin "1") (pinfunction "1_1") (pintype "passive"))
      (node (ref "R41") (pin "2") (pinfunction "2_2") (pintype "passive"))
    )
    (net (code "25") (name "/VSENSE_W") (class "Default")
      (node (ref "J9") (pin "1") (pinfunction "1_1") (pintype "passive"))
      (node (ref "R60") (pin "1") (pinfunction "1_1") (pintype "passive"))
      (node (ref "R62") (pin "2") (pinfunction "2_2") (pintype "passive"))
    )
    (net (code "26") (name "GND") (class "Default")
      (node (ref "C10") (pin "2") (pinfunction "2_2") (pintype "passive"))
      (node (ref "C11") (pin "2") (pinfunction "2_2") (pintype "passive"))
      (node (ref "C12") (pin "1") (pinfunction "1_1") (pintype "passive"))
      (node (ref "C13") (pin "1") (pinfunction "1_1") (pintype "passive"))
      (node (ref "C14") (pin "1") (pinfunction "1_1") (pintype "passive"))
      (node (ref "C15") (pin "1") (pinfunction "1_1") (pintype "passive"))
      (node (ref "C16") (pin "1") (pinfunction "1_1") (pintype "passive"))
      (node (ref "C17") (pin "1") (pinfunction "1_1") (pintype "passive"))
      (node (ref "C18") (pin "1") (pinfunction "1_1") (pintype "passive"))
      (node (ref "C21") (pin "1") (pinfunction "1_1") (pintype "passive"))
      (node (ref "C22") (pin "1") (pinfunction "1_1") (pintype "passive"))
      (node (ref "C23") (pin "1") (pinfunction "1_1") (pintype "passive"))
      (node (ref "C24") (pin "2") (pinfunction "2_2") (pintype "passive"))
      (node (ref "C25") (pin "2") (pinfunction "2_2") (pintype "passive"))
      (node (ref "C26") (pin "2") (pinfunction "2_2") (pintype "passive"))
      (node (ref "C27") (pin "2") (pinfunction "2_2") (pintype "passive"))
      (node (ref "C28") (pin "2") (pinfunction "2_2") (pintype "passive"))
      (node (ref "C29") (pin "2") (pinfunction "2_2") (pintype "passive"))
      (node (ref "C3") (pin "1") (pinfunction "1_1") (pintype "passive"))
      (node (ref "C30") (pin "1") (pinfunction "1_1") (pintype "passive"))
      (node (ref "C31") (pin "1") (pinfunction "1_1") (pintype "passive"))
      (node (ref "C32") (pin "1") (pinfunction "1_1") (pintype "passive"))
      (node (ref "C33") (pin "1") (pinfunction "1_1") (pintype "passive"))
      (node (ref "C34") (pin "1") (pinfunction "1_1") (pintype "passive"))
      (node (ref "C35") (pin "1") (pinfunction "1_1") (pintype "passive"))
      (node (ref "C36") (pin "1") (pinfunction "1_1") (pintype "passive"))
      (node (ref "C37") (pin "2") (pinfunction "2_2") (pintype "passive"))
      (node (ref "C38") (pin "2") (pinfunction "2_2") (pintype "passive"))
      (node (ref "C4") (pin "1") (pinfunction "1_1") (pintype "passive"))
      (node (ref "C41") (pin "1") (pinfunction "1_1") (pintype "passive"))
      (node (ref "C42") (pin "1") (pinfunction "1_1") (pintype "passive"))
      (node (ref "C43") (pin "1") (pinfunction "1_1") (pintype "passive"))
      (node (ref "C44") (pin "2") (pinfunction "2_2") (pintype "passive"))
      (node (ref "C45") (pin "2") (pinfunction "2_2") (pintype "passive"))
      (node (ref "C46") (pin "2") (pinfunction "2_2") (pintype "passive"))
      (node (ref "C47") (pin "2") (pinfunction "2_2") (pintype "passive"))
      (node (ref "C48") (pin "2") (pinfunction "2_2") (pintype "passive"))
      (node (ref "C49") (pin "2") (pinfunction "2_2") (pintype "passive"))
      (node (ref "C5") (pin "1") (pinfunction "1_1") (pintype "passive"))
      (node (ref "C50") (pin "2") (pinfunction "2_2") (pintype "passive"))
      (node (ref "C51") (pin "2") (pinfunction "2_2") (pintype "passive"))
      (node (ref "C52") (pin "2") (pinfunction "2_2") (pintype "passive"))
      (node (ref "C53") (pin "1") (pinfunction "1_1") (pintype "passive"))
      (node (ref "C54") (pin "2") (pinfunction "2_2") (pintype "passive"))
      (node (ref "C55") (pin "1") (pinfunction "1_1") (pintype "passive"))
      (node (ref "C56") (pin "1") (pinfunction "1_1") (pintype "passive"))
      (node (ref "C57") (pin "1") (pinfunction "1_1") (pintype "passive"))
      (node (ref "C58") (pin "1") (pinfunction "1_1") (pintype "passive"))
      (node (ref "C59") (pin "1") (pinfunction "1_1") (pintype "passive"))
      (node (ref "C6") (pin "2") (pinfunction "2_2") (pintype "passive"))
      (node (ref "C60") (pin "1") (pinfunction "1_1") (pintype "passive"))
      (node (ref "C7") (pin "2") (pinfunction "2_2") (pintype "passive"))
      (node (ref "C8") (pin "2") (pinfunction "2_2") (pintype "passive"))
      (node (ref "C9") (pin "2") (pinfunction "2_2") (pintype "passive"))
      (node (ref "J3") (pin "1") (pinfunction "1_1") (pintype "passive"))
      (node (ref "J8") (pin "5") (pinfunction "5_5") (pintype "passive"))
      (node (ref "J8") (pin "7") (pinfunction "7_7") (pintype "passive"))
      (node (ref "J8") (pin "8") (pinfunction "8_8") (pintype "passive"))
      (node (ref "Q13") (pin "SOURCE") (pinfunction "SOURCE_SOURCE") (pintype "passive"))
      (node (ref "Q14") (pin "SOURCE") (pinfunction "SOURCE_SOURCE") (pintype "passive"))
      (node (ref "Q15") (pin "SOURCE") (pinfunction "SOURCE_SOURCE") (pintype "passive"))
      (node (ref "Q16") (pin "SOURCE") (pinfunction "SOURCE_SOURCE") (pintype "passive"))
      (node (ref "Q21") (pin "SOURCE") (pinfunction "SOURCE_SOURCE") (pintype "passive"))
      (node (ref "Q22") (pin "SOURCE") (pinfunction "SOURCE_SOURCE") (pintype "passive"))
      (node (ref "Q23") (pin "SOURCE") (pinfunction "SOURCE_SOURCE") (pintype "passive"))
      (node (ref "Q24") (pin "SOURCE") (pinfunction "SOURCE_SOURCE") (pintype "passive"))
      (node (ref "Q5") (pin "SOURCE") (pinfunction "SOURCE_SOURCE") (pintype "passive"))
      (node (ref "Q6") (pin "SOURCE") (pinfunction "SOURCE_SOURCE") (pintype "passive"))
      (node (ref "Q7") (pin "SOURCE") (pinfunction "SOURCE_SOURCE") (pintype "passive"))
      (node (ref "Q8") (pin "SOURCE") (pinfunction "SOURCE_SOURCE") (pintype "passive"))
      (node (ref "R10") (pin "2") (pinfunction "2_2") (pintype "passive"))
      (node (ref "R12") (pin "1") (pinfunction "1_1") (pintype "passive"))
      (node (ref "R19") (pin "1") (pinfunction "1_1") (pintype "passive"))
      (node (ref "R20") (pin "1") (pinfunction "1_1") (pintype "passive"))
      (node (ref "R23") (pin "1") (pinfunction "1_1") (pintype "passive"))
      (node (ref "R30") (pin "2") (pinfunction "2_2") (pintype "passive"))
      (node (ref "R31") (pin "2") (pinfunction "2_2") (pintype "passive"))
      (node (ref "R32") (pin "2") (pinfunction "2_2") (pintype "passive"))
      (node (ref "R40") (pin "1") (pinfunction "1_1") (pintype "passive"))
      (node (ref "R41") (pin "1") (pinfunction "1_1") (pintype "passive"))
      (node (ref "R43") (pin "1") (pinfunction "1_1") (pintype "passive"))
      (node (ref "R51") (pin "2") (pinfunction "2_2") (pintype "passive"))
      (node (ref "R52") (pin "2") (pinfunction "2_2") (pintype "passive"))
      (node (ref "R53") (pin "2") (pinfunction "2_2") (pintype "passive"))
      (node (ref "R61") (pin "1") (pinfunction "1_1") (pintype "passive"))
      (node (ref "R62") (pin "1") (pinfunction "1_1") (pintype "passive"))
      (node (ref "R64") (pin "1") (pinfunction "1_1") (pintype "passive"))
      (node (ref "R8") (pin "2") (pinfunction "2_2") (pintype "passive"))
      (node (ref "R9") (pin "2") (pinfunction "2_2") (pintype "passive"))
      (node (ref "U1") (pin "4") (pinfunction "GND_4") (pintype "passive"))
      (node (ref "U1") (pin "9") (pinfunction "VSSB_9") (pintype "passive"))
      (node (ref "U2") (pin "2") (pinfunction "GND_2") (pintype "passive"))
      (node (ref "U2") (pin "7") (pinfunction "REF1_7") (pintype "passive"))
      (node (ref "U3") (pin "4") (pinfunction "GND_4") (pintype "passive"))
      (node (ref "U3") (pin "9") (pinfunction "VSSB_9") (pintype "passive"))
      (node (ref "U4") (pin "2") (pinfunction "GND_2") (pintype "passive"))
      (node (ref "U4") (pin "7") (pinfunction "REF1_7") (pintype "passive"))
      (node (ref "U5") (pin "4") (pinfunction "GND_4") (pintype "passive"))
      (node (ref "U5") (pin "9") (pinfunction "VSSB_9") (pintype "passive"))
      (node (ref "U6") (pin "2") (pinfunction "GND_2") (pintype "passive"))
      (node (ref "U6") (pin "7") (pinfunction "REF1_7") (pintype "passive"))
    )
    (net (code "27") (name "Net-(D1-K)") (class "Default")
      (node (ref "C1") (pin "2") (pinfunction "2_2") (pintype "passive"))
      (node (ref "C2") (pin "2") (pinfunction "2_2") (pintype "passive"))
      (node (ref "D1") (pin "C") (pinfunction "K_C") (pintype "passive"))
      (node (ref "U1") (pin "16") (pinfunction "VDDA_16") (pintype "passive"))
    )
    (net (code "28") (name "Net-(D1-PadA)") (class "Default")
      (node (ref "D1") (pin "A") (pinfunction "A_A") (pintype "passive"))
      (node (ref "R1") (pin "2") (pinfunction "2_2") (pintype "passive"))
    )
    (net (code "29") (name "Net-(D2-PadA)") (class "Default")
      (node (ref "D2") (pin "A") (pinfunction "A_A") (pintype "passive"))
      (node (ref "R5") (pin "1") (pinfunction "1_1") (pintype "passive"))
    )
    (net (code "30") (name "Net-(D3-PadA)") (class "Default")
      (node (ref "D3") (pin "A") (pinfunction "A_A") (pintype "passive"))
      (node (ref "R22") (pin "2") (pinfunction "2_2") (pintype "passive"))
    )
    (net (code "31") (name "Net-(D4-K)") (class "Default")
      (node (ref "C19") (pin "2") (pinfunction "2_2") (pintype "passive"))
      (node (ref "C20") (pin "2") (pinfunction "2_2") (pintype "passive"))
      (node (ref "D4") (pin "C") (pinfunction "K_C") (pintype "passive"))
      (node (ref "U3") (pin "16") (pinfunction "VDDA_16") (pintype "passive"))
    )
    (net (code "32") (name "Net-(D4-PadA)") (class "Default")
      (node (ref "D4") (pin "A") (pinfunction "A_A") (pintype "passive"))
      (node (ref "R24") (pin "2") (pinfunction "2_2") (pintype "passive"))
    )
    (net (code "33") (name "Net-(D5-PadA)") (class "Default")
      (node (ref "D5") (pin "A") (pinfunction "A_A") (pintype "passive"))
      (node (ref "R27") (pin "1") (pinfunction "1_1") (pintype "passive"))
    )
    (net (code "34") (name "Net-(D6-PadA)") (class "Default")
      (node (ref "D6") (pin "A") (pinfunction "A_A") (pintype "passive"))
      (node (ref "R44") (pin "2") (pinfunction "2_2") (pintype "passive"))
    )
    (net (code "35") (name "Net-(D7-K)") (class "Default")
      (node (ref "C39") (pin "2") (pinfunction "2_2") (pintype "passive"))
      (node (ref "C40") (pin "2") (pinfunction "2_2") (pintype "passive"))
      (node (ref "D7") (pin "C") (pinfunction "K_C") (pintype "passive"))
      (node (ref "U5") (pin "16") (pinfunction "VDDA_16") (pintype "passive"))
    )
    (net (code "36") (name "Net-(D7-PadA)") (class "Default")
      (node (ref "D7") (pin "A") (pinfunction "A_A") (pintype "passive"))
      (node (ref "R45") (pin "2") (pinfunction "2_2") (pintype "passive"))
    )
    (net (code "37") (name "Net-(D8-PadA)") (class "Default")
      (node (ref "D8") (pin "A") (pinfunction "A_A") (pintype "passive"))
      (node (ref "R48") (pin "1") (pinfunction "1_1") (pintype "passive"))
    )
    (net (code "38") (name "Net-(D9-PadA)") (class "Default")
      (node (ref "D9") (pin "A") (pinfunction "A_A") (pintype "passive"))
      (node (ref "R65") (pin "2") (pinfunction "2_2") (pintype "passive"))
    )
    (net (code "39") (name "Net-(Q1-PadGATE)") (class "Default")
      (node (ref "Q1") (pin "GATE") (pinfunction "GATE_GATE") (pintype "passive"))
      (node (ref "Q2") (pin "GATE") (pinfunction "GATE_GATE") (pintype "passive"))
      (node (ref "Q3") (pin "GATE") (pinfunction "GATE_GATE") (pintype "passive"))
      (node (ref "Q4") (pin "GATE") (pinfunction "GATE_GATE") (pintype "passive"))
      (node (ref "R5") (pin "2") (pinfunction "2_2") (pintype "passive"))
      (node (ref "R7") (pin "2") (pinfunction "2_2") (pintype "passive"))
    )
    (net (code "40") (name "Net-(Q5-PadGATE)") (class "Default")
      (node (ref "Q5") (pin "GATE") (pinfunction "GATE_GATE") (pintype "passive"))
      (node (ref "Q6") (pin "GATE") (pinfunction "GATE_GATE") (pintype "passive"))
      (node (ref "Q7") (pin "GATE") (pinfunction "GATE_GATE") (pintype "passive"))
      (node (ref "Q8") (pin "GATE") (pinfunction "GATE_GATE") (pintype "passive"))
      (node (ref "R21") (pin "1") (pinfunction "1_1") (pintype "passive"))
      (node (ref "R22") (pin "1") (pinfunction "1_1") (pintype "passive"))
    )
    (net (code "41") (name "Net-(Q10-PadGATE)") (class "Default")
      (node (ref "Q10") (pin "GATE") (pinfunction "GATE_GATE") (pintype "passive"))
      (node (ref "Q11") (pin "GATE") (pinfunction "GATE_GATE") (pintype "passive"))
      (node (ref "Q12") (pin "GATE") (pinfunction "GATE_GATE") (pintype "passive"))
      (node (ref "Q9") (pin "GATE") (pinfunction "GATE_GATE") (pintype "passive"))
      (node (ref "R27") (pin "2") (pinfunction "2_2") (pintype "passive"))
      (node (ref "R29") (pin "2") (pinfunction "2_2") (pintype "passive"))
    )
    (net (code "42") (name "Net-(Q13-PadGATE)") (class "Default")
      (node (ref "Q13") (pin "GATE") (pinfunction "GATE_GATE") (pintype "passive"))
      (node (ref "Q14") (pin "GATE") (pinfunction "GATE_GATE") (pintype "passive"))
      (node (ref "Q15") (pin "GATE") (pinfunction "GATE_GATE") (pintype "passive"))
      (node (ref "Q16") (pin "GATE") (pinfunction "GATE_GATE") (pintype "passive"))
      (node (ref "R42") (pin "1") (pinfunction "1_1") (pintype "passive"))
      (node (ref "R44") (pin "1") (pinfunction "1_1") (pintype "passive"))
    )
    (net (code "43") (name "Net-(Q17-PadGATE)") (class "Default")
      (node (ref "Q17") (pin "GATE") (pinfunction "GATE_GATE") (pintype "passive"))
      (node (ref "Q18") (pin "GATE") (pinfunction "GATE_GATE") (pintype "passive"))
      (node (ref "Q19") (pin "GATE") (pinfunction "GATE_GATE") (pintype "passive"))
      (node (ref "Q20") (pin "GATE") (pinfunction "GATE_GATE") (pintype "passive"))
      (node (ref "R48") (pin "2") (pinfunction "2_2") (pintype "passive"))
      (node (ref "R50") (pin "2") (pinfunction "2_2") (pintype "passive"))
    )
    (net (code "44") (name "Net-(Q21-PadGATE)") (class "Default")
      (node (ref "Q21") (pin "GATE") (pinfunction "GATE_GATE") (pintype "passive"))
      (node (ref "Q22") (pin "GATE") (pinfunction "GATE_GATE") (pintype "passive"))
      (node (ref "Q23") (pin "GATE") (pinfunction "GATE_GATE") (pintype "passive"))
      (node (ref "Q24") (pin "GATE") (pinfunction "GATE_GATE") (pintype "passive"))
      (node (ref "R63") (pin "1") (pinfunction "1_1") (pintype "passive"))
      (node (ref "R65") (pin "1") (pinfunction "1_1") (pintype "passive"))
    )
    (net (code "45") (name "Net-(U1-DISABLE)") (class "Default")
      (node (ref "C6") (pin "1") (pinfunction "1_1") (pintype "passive"))
      (node (ref "R16") (pin "2") (pinfunction "2_2") (pintype "passive"))
      (node (ref "R8") (pin "1") (pinfunction "1_1") (pintype "passive"))
      (node (ref "U1") (pin "5") (pinfunction "DISABLE_5") (pintype "passive"))
    )
    (net (code "46") (name "Net-(U1-DT)") (class "Default")
      (node (ref "C12") (pin "2") (pinfunction "2_2") (pintype "passive"))
      (node (ref "R19") (pin "2") (pinfunction "2_2") (pintype "passive"))
      (node (ref "U1") (pin "6") (pinfunction "DT_6") (pintype "passive"))
    )
    (net (code "47") (name "Net-(U1-INA)") (class "Default")
      (node (ref "C8") (pin "1") (pinfunction "1_1") (pintype "passive"))
      (node (ref "R10") (pin "1") (pinfunction "1_1") (pintype "passive"))
      (node (ref "R13") (pin "2") (pinfunction "2_2") (pintype "passive"))
      (node (ref "U1") (pin "1") (pinfunction "INA_1") (pintype "passive"))
    )
    (net (code "48") (name "Net-(U1-INB)") (class "Default")
      (node (ref "C7") (pin "1") (pinfunction "1_1") (pintype "passive"))
      (node (ref "R15") (pin "2") (pinfunction "2_2") (pintype "passive"))
      (node (ref "R9") (pin "1") (pinfunction "1_1") (pintype "passive"))
      (node (ref "U1") (pin "2") (pinfunction "INB_2") (pintype "passive"))
    )
    (net (code "49") (name "Net-(U1-OUTA)") (class "Default")
      (node (ref "D2") (pin "C") (pinfunction "C_C") (pintype "passive"))
      (node (ref "R7") (pin "1") (pinfunction "1_1") (pintype "passive"))
      (node (ref "U1") (pin "15") (pinfunction "OUTA_15") (pintype "passive"))
    )
    (net (code "50") (name "Net-(U1-OUTB)") (class "Default")
      (node (ref "D3") (pin "C") (pinfunction "C_C") (pintype "passive"))
      (node (ref "R21") (pin "2") (pinfunction "2_2") (pintype "passive"))
      (node (ref "U1") (pin "10") (pinfunction "OUTB_10") (pintype "passive"))
    )
    (net (code "51") (name "Net-(U2-OUT)") (class "Default")
      (node (ref "R17") (pin "1") (pinfunction "1_1") (pintype "passive"))
      (node (ref "U2") (pin "5") (pinfunction "OUT_5") (pintype "passive"))
    )
    (net (code "52") (name "Net-(U3-DISABLE)") (class "Default")
      (node (ref "C24") (pin "1") (pinfunction "1_1") (pintype "passive"))
      (node (ref "R30") (pin "1") (pinfunction "1_1") (pintype "passive"))
      (node (ref "R37") (pin "2") (pinfunction "2_2") (pintype "passive"))
      (node (ref "U3") (pin "5") (pinfunction "DISABLE_5") (pintype "passive"))
    )
    (net (code "53") (name "Net-(U3-DT)") (class "Default")
      (node (ref "C30") (pin "2") (pinfunction "2_2") (pintype "passive"))
      (node (ref "R40") (pin "2") (pinfunction "2_2") (pintype "passive"))
      (node (ref "U3") (pin "6") (pinfunction "DT_6") (pintype "passive"))
    )
    (net (code "54") (name "Net-(U3-INA)") (class "Default")
      (node (ref "C26") (pin "1") (pinfunction "1_1") (pintype "passive"))
      (node (ref "R32") (pin "1") (pinfunction "1_1") (pintype "passive"))
      (node (ref "R34") (pin "2") (pinfunction "2_2") (pintype "passive"))
      (node (ref "U3") (pin "1") (pinfunction "INA_1") (pintype "passive"))
    )
    (net (code "55") (name "Net-(U3-INB)") (class "Default")
      (node (ref "C25") (pin "1") (pinfunction "1_1") (pintype "passive"))
      (node (ref "R31") (pin "1") (pinfunction "1_1") (pintype "passive"))
      (node (ref "R36") (pin "2") (pinfunction "2_2") (pintype "passive"))
      (node (ref "U3") (pin "2") (pinfunction "INB_2") (pintype "passive"))
    )
    (net (code "56") (name "Net-(U3-OUTA)") (class "Default")
      (node (ref "D5") (pin "C") (pinfunction "C_C") (pintype "passive"))
      (node (ref "R29") (pin "1") (pinfunction "1_1") (pintype "passive"))
      (node (ref "U3") (pin "15") (pinfunction "OUTA_15") (pintype "passive"))
    )
    (net (code "57") (name "Net-(U3-OUTB)") (class "Default")
      (node (ref "D6") (pin "C") (pinfunction "C_C") (pintype "passive"))
      (node (ref "R42") (pin "2") (pinfunction "2_2") (pintype "passive"))
      (node (ref "U3") (pin "10") (pinfunction "OUTB_10") (pintype "passive"))
    )
    (net (code "58") (name "Net-(U4-OUT)") (class "Default")
      (node (ref "R38") (pin "1") (pinfunction "1_1") (pintype "passive"))
      (node (ref "U4") (pin "5") (pinfunction "OUT_5") (pintype "passive"))
    )
    (net (code "59") (name "Net-(U5-DISABLE)") (class "Default")
      (node (ref "C44") (pin "1") (pinfunction "1_1") (pintype "passive"))
      (node (ref "R51") (pin "1") (pinfunction "1_1") (pintype "passive"))
      (node (ref "R58") (pin "2") (pinfunction "2_2") (pintype "passive"))
      (node (ref "U5") (pin "5") (pinfunction "DISABLE_5") (pintype "passive"))
    )
    (net (code "60") (name "Net-(U5-DT)") (class "Default")
      (node (ref "C53") (pin "2") (pinfunction "2_2") (pintype "passive"))
      (node (ref "R61") (pin "2") (pinfunction "2_2") (pintype "passive"))
      (node (ref "U5") (pin "6") (pinfunction "DT_6") (pintype "passive"))
    )
    (net (code "61") (name "Net-(U5-INA)") (class "Default")
      (node (ref "C46") (pin "1") (pinfunction "1_1") (pintype "passive"))
      (node (ref "R53") (pin "1") (pinfunction "1_1") (pintype "passive"))
      (node (ref "R55") (pin "2") (pinfunction "2_2") (pintype "passive"))
      (node (ref "U5") (pin "1") (pinfunction "INA_1") (pintype "passive"))
    )
    (net (code "62") (name "Net-(U5-INB)") (class "Default")
      (node (ref "C45") (pin "1") (pinfunction "1_1") (pintype "passive"))
      (node (ref "R52") (pin "1") (pinfunction "1_1") (pintype "passive"))
      (node (ref "R57") (pin "2") (pinfunction "2_2") (pintype "passive"))
      (node (ref "U5") (pin "2") (pinfunction "INB_2") (pintype "passive"))
    )
    (net (code "63") (name "Net-(U5-OUTA)") (class "Default")
      (node (ref "D8") (pin "C") (pinfunction "C_C") (pintype "passive"))
      (node (ref "R50") (pin "1") (pinfunction "1_1") (pintype "passive"))
      (node (ref "U5") (pin "15") (pinfunction "OUTA_15") (pintype "passive"))
    )
    (net (code "64") (name "Net-(U5-OUTB)") (class "Default")
      (node (ref "D9") (pin "C") (pinfunction "C_C") (pintype "passive"))
      (node (ref "R63") (pin "2") (pinfunction "2_2") (pintype "passive"))
      (node (ref "U5") (pin "10") (pinfunction "OUTB_10") (pintype "passive"))
    )
    (net (code "65") (name "Net-(U6-OUT)") (class "Default")
      (node (ref "R59") (pin "1") (pinfunction "1_1") (pintype "passive"))
      (node (ref "U6") (pin "5") (pinfunction "OUT_5") (pintype "passive"))
    )
    (net (code "66") (name "VIN+") (class "Default")
      (node (ref "C10") (pin "1") (pinfunction "1_1") (pintype "passive"))
      (node (ref "C11") (pin "1") (pinfunction "1_1") (pintype "passive"))
      (node (ref "C21") (pin "2") (pinfunction "2_2") (pintype "passive"))
      (node (ref "C22") (pin "2") (pinfunction "2_2") (pintype "passive"))
      (node (ref "C23") (pin "2") (pinfunction "2_2") (pintype "passive"))
      (node (ref "C27") (pin "1") (pinfunction "1_1") (pintype "passive"))
      (node (ref "C28") (pin "1") (pinfunction "1_1") (pintype "passive"))
      (node (ref "C29") (pin "1") (pinfunction "1_1") (pintype "passive"))
      (node (ref "C3") (pin "2") (pinfunction "2_2") (pintype "passive"))
      (node (ref "C37") (pin "1") (pinfunction "1_1") (pintype "passive"))
      (node (ref "C38") (pin "1") (pinfunction "1_1") (pintype "passive"))
      (node (ref "C4") (pin "2") (pinfunction "2_2") (pintype "passive"))
      (node (ref "C41") (pin "2") (pinfunction "2_2") (pintype "passive"))
      (node (ref "C42") (pin "2") (pinfunction "2_2") (pintype "passive"))
      (node (ref "C43") (pin "2") (pinfunction "2_2") (pintype "passive"))
      (node (ref "C47") (pin "1") (pinfunction "1_1") (pintype "passive"))
      (node (ref "C48") (pin "1") (pinfunction "1_1") (pintype "passive"))
      (node (ref "C49") (pin "1") (pinfunction "1_1") (pintype "passive"))
      (node (ref "C5") (pin "2") (pinfunction "2_2") (pintype "passive"))
      (node (ref "C50") (pin "1") (pinfunction "1_1") (pintype "passive"))
      (node (ref "C51") (pin "1") (pinfunction "1_1") (pintype "passive"))
      (node (ref "C52") (pin "1") (pinfunction "1_1") (pintype "passive"))
      (node (ref "C54") (pin "1") (pinfunction "1_1") (pintype "passive"))
      (node (ref "C9") (pin "1") (pinfunction "1_1") (pintype "passive"))
      (node (ref "J2") (pin "1") (pinfunction "1_1") (pintype "passive"))
      (node (ref "Q1") (pin "DRAIN") (pinfunction "DRAIN_DRAIN") (pintype "passive"))
      (node (ref "Q10") (pin "DRAIN") (pinfunction "DRAIN_DRAIN") (pintype "passive"))
      (node (ref "Q11") (pin "DRAIN") (pinfunction "DRAIN_DRAIN") (pintype "passive"))
      (node (ref "Q12") (pin "DRAIN") (pinfunction "DRAIN_DRAIN") (pintype "passive"))
      (node (ref "Q17") (pin "DRAIN") (pinfunction "DRAIN_DRAIN") (pintype "passive"))
      (node (ref "Q18") (pin "DRAIN") (pinfunction "DRAIN_DRAIN") (pintype "passive"))
      (node (ref "Q19") (pin "DRAIN") (pinfunction "DRAIN_DRAIN") (pintype "passive"))
      (node (ref "Q2") (pin "DRAIN") (pinfunction "DRAIN_DRAIN") (pintype "passive"))
      (node (ref "Q20") (pin "DRAIN") (pinfunction "DRAIN_DRAIN") (pintype "passive"))
      (node (ref "Q3") (pin "DRAIN") (pinfunction "DRAIN_DRAIN") (pintype "passive"))
      (node (ref "Q4") (pin "DRAIN") (pinfunction "DRAIN_DRAIN") (pintype "passive"))
      (node (ref "Q9") (pin "DRAIN") (pinfunction "DRAIN_DRAIN") (pintype "passive"))
      (node (ref "R4") (pin "2") (pinfunction "2_2") (pintype "passive"))
    )
    (net (code "67") (name "unconnected-(U1-NC_1-Pad7)") (class "Default")
      (node (ref "U1") (pin "7") (pinfunction "NC_1_7") (pintype "passive"))
    )
    (net (code "68") (name "unconnected-(U1-NC_2-Pad12)") (class "Default")
      (node (ref "U1") (pin "12") (pinfunction "NC_2_12") (pintype "passive"))
    )
    (net (code "69") (name "unconnected-(U1-NC_3-Pad13)") (class "Default")
      (node (ref "U1") (pin "13") (pinfunction "NC_3_13") (pintype "passive"))
    )
    (net (code "70") (name "unconnected-(U3-NC_1-Pad7)") (class "Default")
      (node (ref "U3") (pin "7") (pinfunction "NC_1_7") (pintype "passive"))
    )
    (net (code "71") (name "unconnected-(U3-NC_2-Pad12)") (class "Default")
      (node (ref "U3") (pin "12") (pinfunction "NC_2_12") (pintype "passive"))
    )
    (net (code "72") (name "unconnected-(U3-NC_3-Pad13)") (class "Default")
      (node (ref "U3") (pin "13") (pinfunction "NC_3_13") (pintype "passive"))
    )
    (net (code "73") (name "unconnected-(U5-NC_1-Pad7)") (class "Default")
      (node (ref "U5") (pin "7") (pinfunction "NC_1_7") (pintype "passive"))
    )
    (net (code "74") (name "unconnected-(U5-NC_2-Pad12)") (class "Default")
      (node (ref "U5") (pin "12") (pinfunction "NC_2_12") (pintype "passive"))
    )
    (net (code "75") (name "unconnected-(U5-NC_3-Pad13)") (class "Default")
      (node (ref "U5") (pin "13") (pinfunction "NC_3_13") (pintype "passive"))
    )
  )
)
